# Eagle_LEDCUBE2.net
KiCad netlist of a schematic drawn in EAGLE
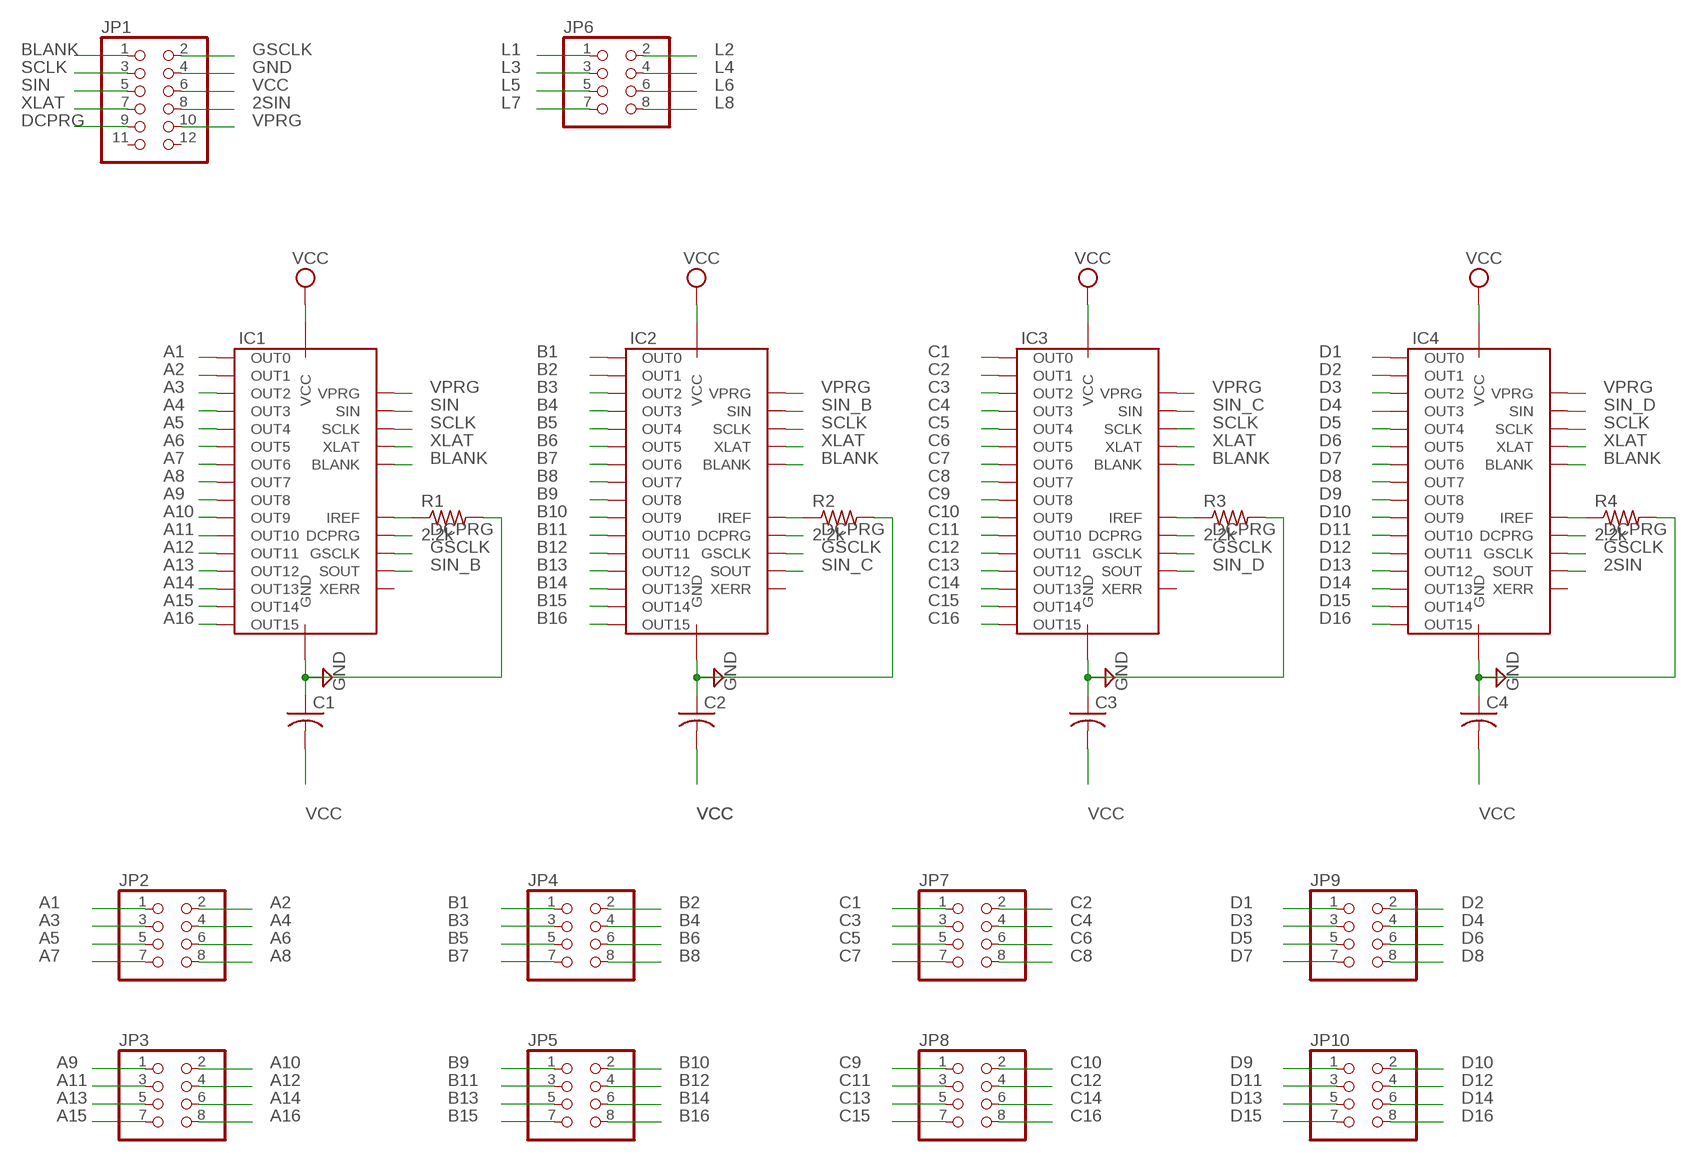
[diagram p0: schematic, sheet 1]
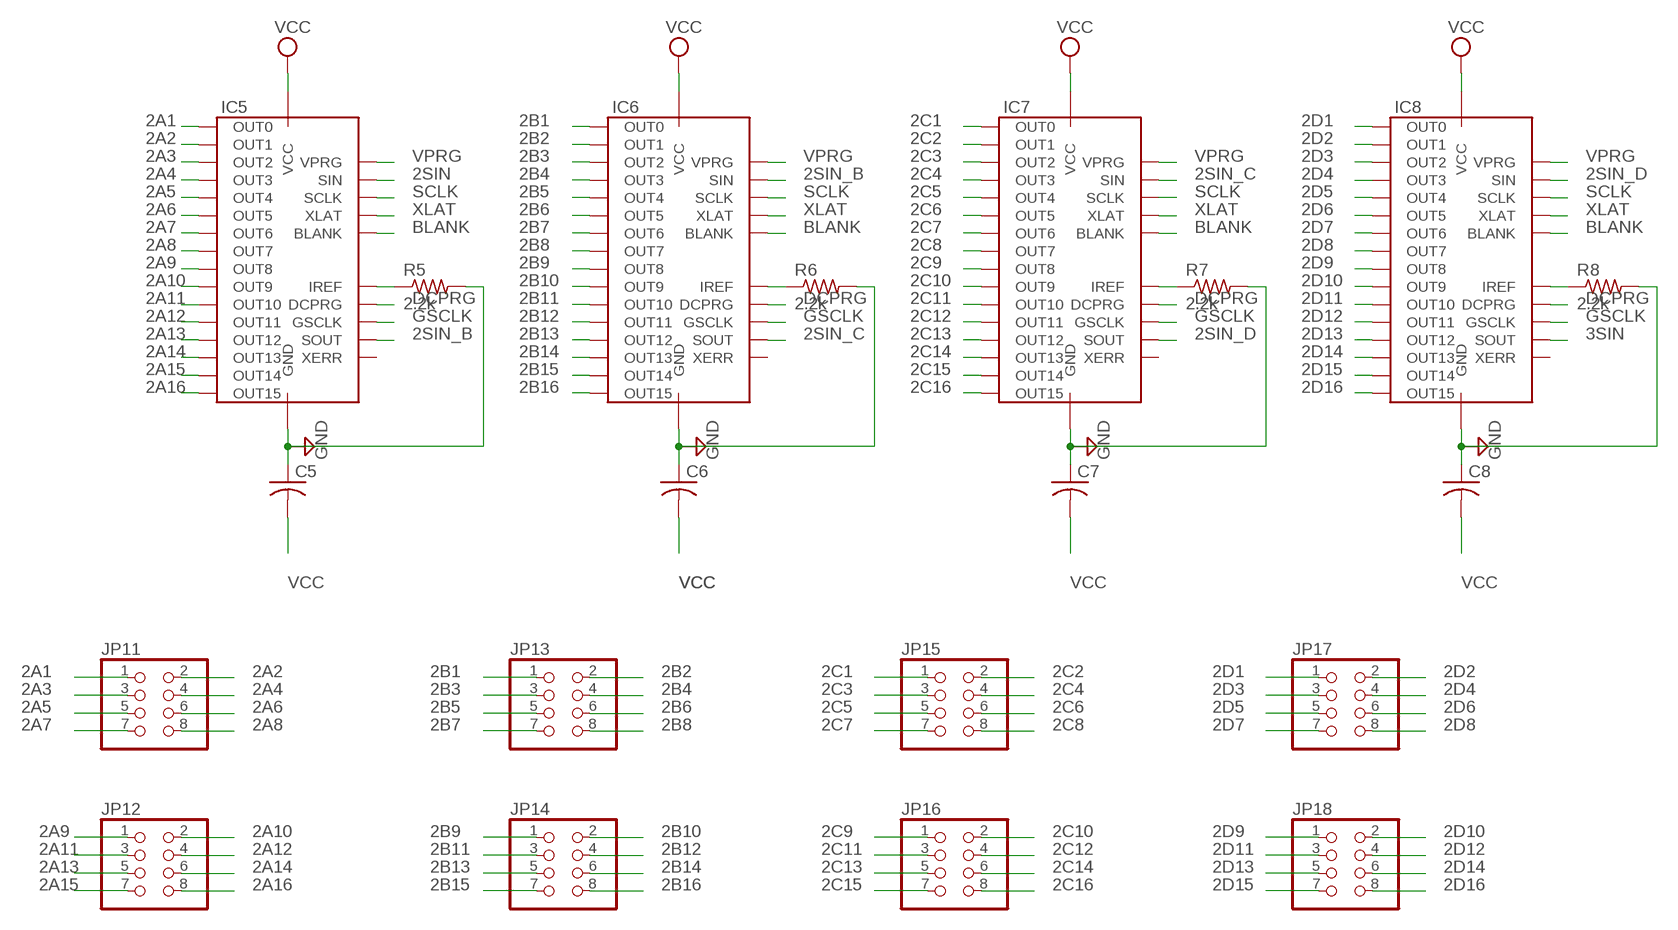
[diagram p1: schematic, sheet 2]
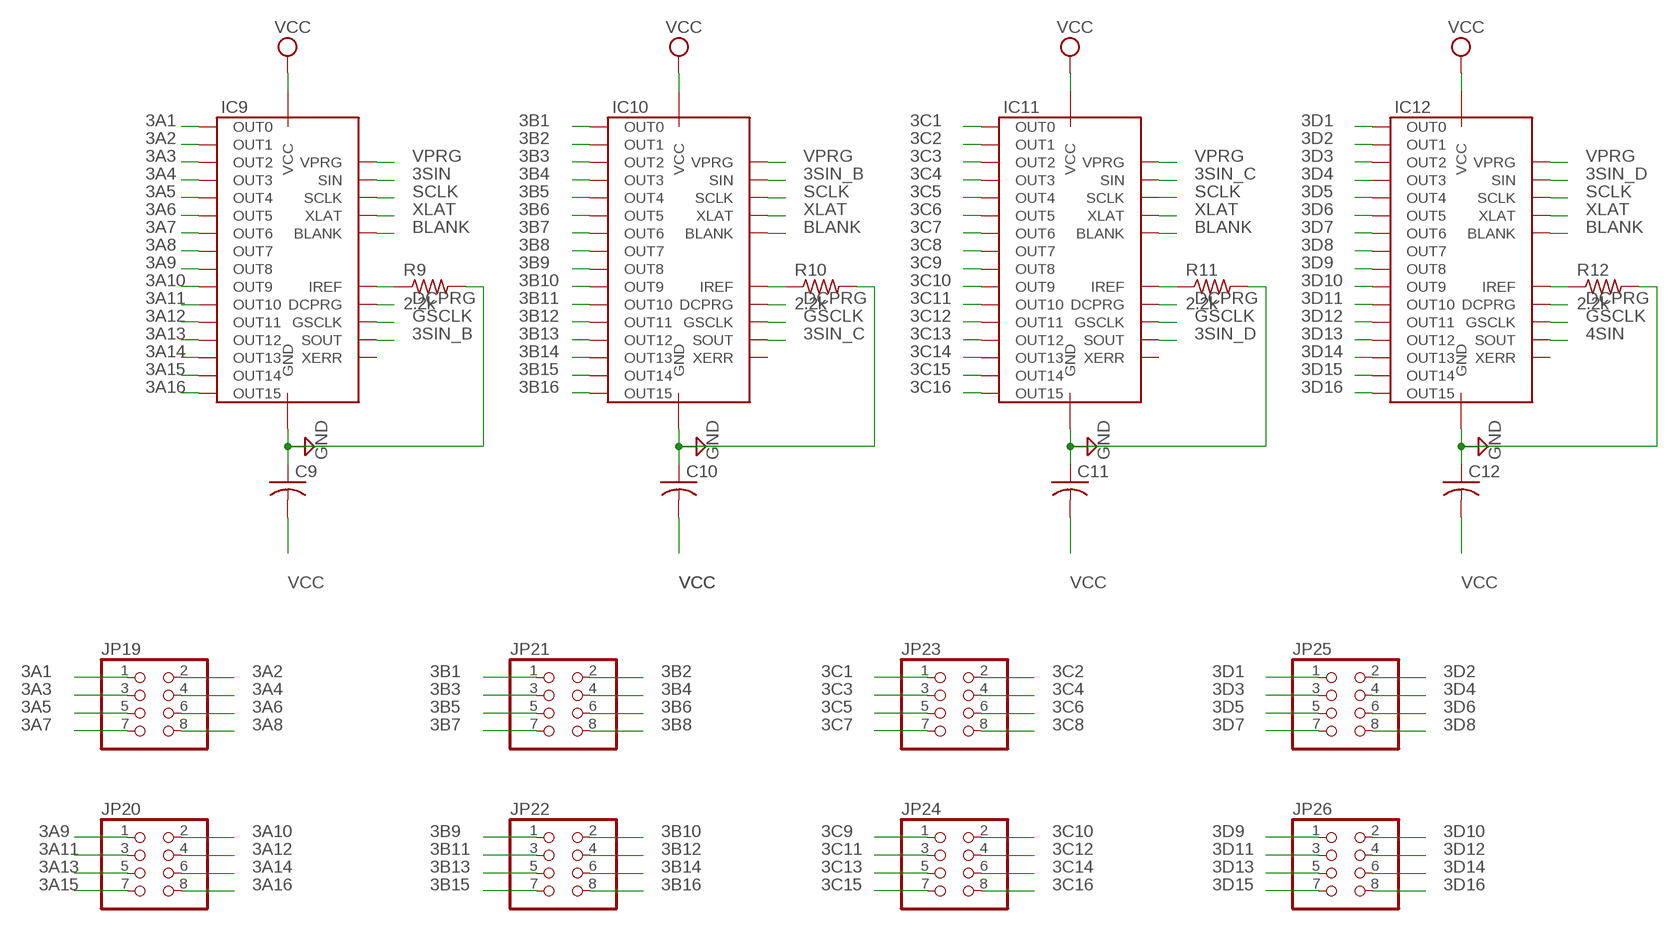
[diagram p2: schematic, sheet 3]
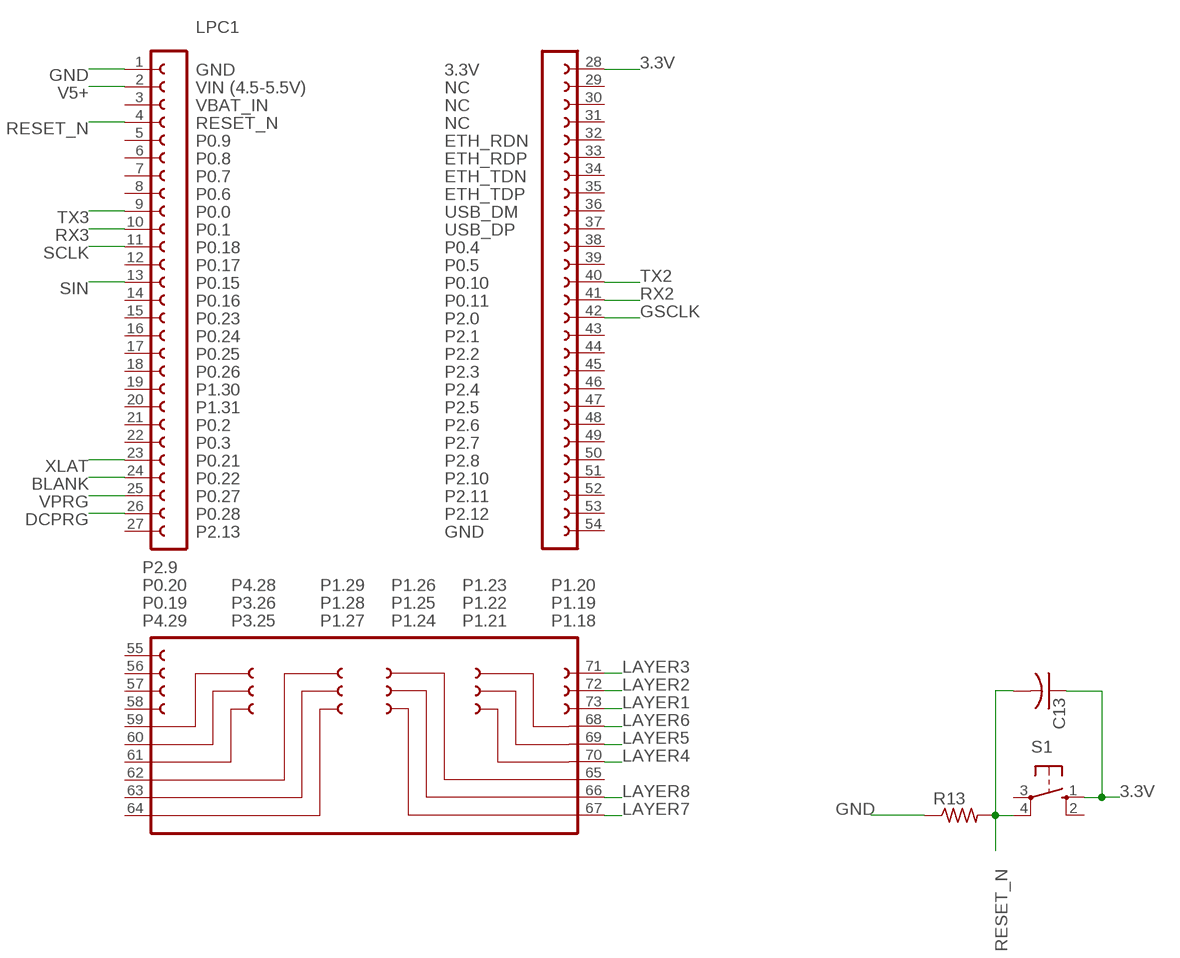
[diagram p3: schematic, sheet 4]
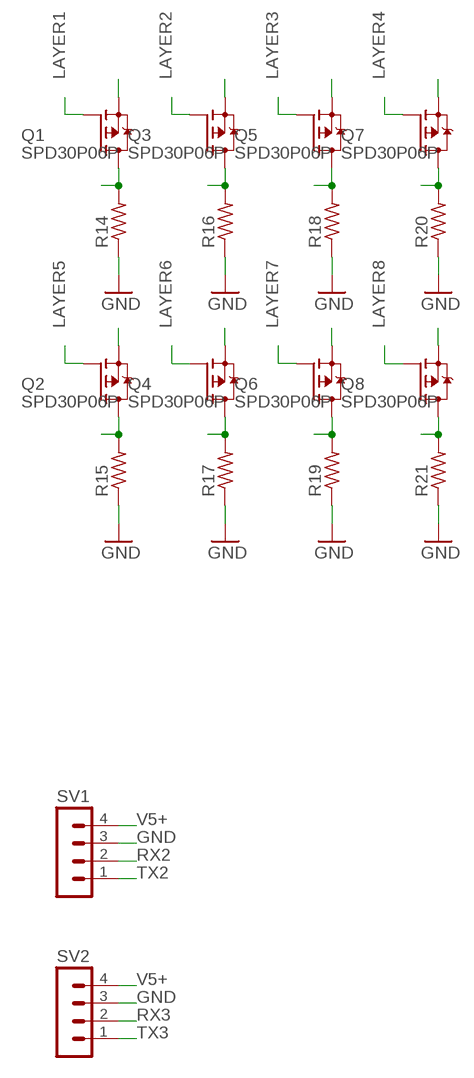
[diagram p4: schematic, sheet 5]
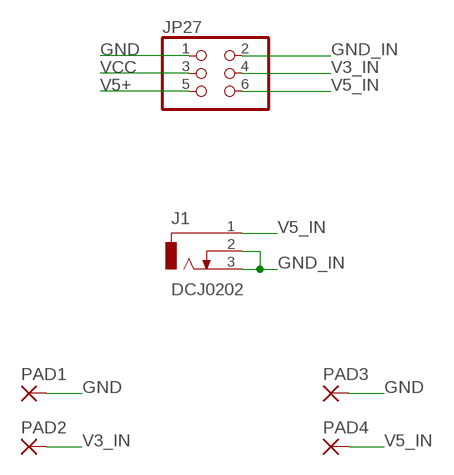
[diagram p5: schematic, sheet 6]

(export (version "E")
  (design (tool "Eeschema 10.0.6"))
  (components
    (comp (ref "Q1")
      (value "SPD30P06P")
      (footprint "eagle-import:TO251AA")
      (libsource (lib "eagle-import") (part "SPD30P06P"))
    )
    (comp (ref "Q2")
      (value "SPD30P06P")
      (footprint "eagle-import:TO251AA")
      (libsource (lib "eagle-import") (part "SPD30P06P"))
    )
    (comp (ref "Q3")
      (value "SPD30P06P")
      (footprint "eagle-import:TO251AA")
      (libsource (lib "eagle-import") (part "SPD30P06P"))
    )
    (comp (ref "Q4")
      (value "SPD30P06P")
      (footprint "eagle-import:TO251AA")
      (libsource (lib "eagle-import") (part "SPD30P06P"))
    )
    (comp (ref "Q5")
      (value "SPD30P06P")
      (footprint "eagle-import:TO251AA")
      (libsource (lib "eagle-import") (part "SPD30P06P"))
    )
    (comp (ref "Q6")
      (value "SPD30P06P")
      (footprint "eagle-import:TO251AA")
      (libsource (lib "eagle-import") (part "SPD30P06P"))
    )
    (comp (ref "Q7")
      (value "SPD30P06P")
      (footprint "eagle-import:TO251AA")
      (libsource (lib "eagle-import") (part "SPD30P06P"))
    )
    (comp (ref "Q8")
      (value "SPD30P06P")
      (footprint "eagle-import:TO251AA")
      (libsource (lib "eagle-import") (part "SPD30P06P"))
    )
    (comp (ref "R14")
      (value "R-US_R0805")
      (footprint "eagle-import:R0805")
      (libsource (lib "eagle-import") (part "resistor_R-US_R0805"))
    )
    (comp (ref "R15")
      (value "R-US_R0805")
      (footprint "eagle-import:R0805")
      (libsource (lib "eagle-import") (part "resistor_R-US_R0805"))
    )
    (comp (ref "R16")
      (value "R-US_R0805")
      (footprint "eagle-import:R0805")
      (libsource (lib "eagle-import") (part "resistor_R-US_R0805"))
    )
    (comp (ref "R17")
      (value "R-US_R0805")
      (footprint "eagle-import:R0805")
      (libsource (lib "eagle-import") (part "resistor_R-US_R0805"))
    )
    (comp (ref "R18")
      (value "R-US_R0805")
      (footprint "eagle-import:R0805")
      (libsource (lib "eagle-import") (part "resistor_R-US_R0805"))
    )
    (comp (ref "R19")
      (value "R-US_R0805")
      (footprint "eagle-import:R0805")
      (libsource (lib "eagle-import") (part "resistor_R-US_R0805"))
    )
    (comp (ref "R20")
      (value "R-US_R0805")
      (footprint "eagle-import:R0805")
      (libsource (lib "eagle-import") (part "resistor_R-US_R0805"))
    )
    (comp (ref "R21")
      (value "R-US_R0805")
      (footprint "eagle-import:R0805")
      (libsource (lib "eagle-import") (part "resistor_R-US_R0805"))
    )
    (comp (ref "SV1")
      (value "MA04-1")
      (footprint "eagle-import:MA04-1")
      (libsource (lib "eagle-import") (part "MA04-1"))
    )
    (comp (ref "SV2")
      (value "MA04-1")
      (footprint "eagle-import:MA04-1")
      (libsource (lib "eagle-import") (part "MA04-1"))
    )
    (comp (ref "C5")
      (value "C-USC0805K")
      (footprint "eagle-import:C0805K")
      (libsource (lib "eagle-import") (part "resistor_C-USC0805K"))
    )
    (comp (ref "C6")
      (value "C-USC0805K")
      (footprint "eagle-import:C0805K")
      (libsource (lib "eagle-import") (part "resistor_C-USC0805K"))
    )
    (comp (ref "C7")
      (value "C-USC0805K")
      (footprint "eagle-import:C0805K")
      (libsource (lib "eagle-import") (part "resistor_C-USC0805K"))
    )
    (comp (ref "C8")
      (value "C-USC0805K")
      (footprint "eagle-import:C0805K")
      (libsource (lib "eagle-import") (part "resistor_C-USC0805K"))
    )
    (comp (ref "IC5")
      (value "IC-PACKAGE_DIL28-1")
      (footprint "eagle-import:IC-SSOP28")
      (libsource (lib "eagle-import") (part "IC-PACKAGE_DIL28-1"))
    )
    (comp (ref "IC6")
      (value "IC-PACKAGE_DIL28-1")
      (footprint "eagle-import:IC-SSOP28")
      (libsource (lib "eagle-import") (part "IC-PACKAGE_DIL28-1"))
    )
    (comp (ref "IC7")
      (value "IC-PACKAGE_DIL28-1")
      (footprint "eagle-import:IC-SSOP28")
      (libsource (lib "eagle-import") (part "IC-PACKAGE_DIL28-1"))
    )
    (comp (ref "IC8")
      (value "IC-PACKAGE_DIL28-1")
      (footprint "eagle-import:IC-SSOP28")
      (libsource (lib "eagle-import") (part "IC-PACKAGE_DIL28-1"))
    )
    (comp (ref "JP11")
      (value "PINHD-2X4")
      (footprint "eagle-import:2X04")
      (libsource (lib "eagle-import") (part "PINHD-2X4"))
    )
    (comp (ref "JP12")
      (value "PINHD-2X4")
      (footprint "eagle-import:2X04")
      (libsource (lib "eagle-import") (part "PINHD-2X4"))
    )
    (comp (ref "JP13")
      (value "PINHD-2X4")
      (footprint "eagle-import:2X04")
      (libsource (lib "eagle-import") (part "PINHD-2X4"))
    )
    (comp (ref "JP14")
      (value "PINHD-2X4")
      (footprint "eagle-import:2X04")
      (libsource (lib "eagle-import") (part "PINHD-2X4"))
    )
    (comp (ref "JP15")
      (value "PINHD-2X4")
      (footprint "eagle-import:2X04")
      (libsource (lib "eagle-import") (part "PINHD-2X4"))
    )
    (comp (ref "JP16")
      (value "PINHD-2X4")
      (footprint "eagle-import:2X04")
      (libsource (lib "eagle-import") (part "PINHD-2X4"))
    )
    (comp (ref "JP17")
      (value "PINHD-2X4")
      (footprint "eagle-import:2X04")
      (libsource (lib "eagle-import") (part "PINHD-2X4"))
    )
    (comp (ref "JP18")
      (value "PINHD-2X4")
      (footprint "eagle-import:2X04")
      (libsource (lib "eagle-import") (part "PINHD-2X4"))
    )
    (comp (ref "R5")
      (value "2.2k")
      (footprint "eagle-import:R0805")
      (libsource (lib "eagle-import") (part "resistor_R-US_R0805"))
    )
    (comp (ref "R6")
      (value "2.2k")
      (footprint "eagle-import:R0805")
      (libsource (lib "eagle-import") (part "resistor_R-US_R0805"))
    )
    (comp (ref "R7")
      (value "2.2k")
      (footprint "eagle-import:R0805")
      (libsource (lib "eagle-import") (part "resistor_R-US_R0805"))
    )
    (comp (ref "R8")
      (value "2.2k")
      (footprint "eagle-import:R0805")
      (libsource (lib "eagle-import") (part "resistor_R-US_R0805"))
    )
    (comp (ref "C9")
      (value "C-USC0805K")
      (footprint "eagle-import:C0805K")
      (libsource (lib "eagle-import") (part "resistor_C-USC0805K"))
    )
    (comp (ref "C10")
      (value "C-USC0805K")
      (footprint "eagle-import:C0805K")
      (libsource (lib "eagle-import") (part "resistor_C-USC0805K"))
    )
    (comp (ref "C11")
      (value "C-USC0805K")
      (footprint "eagle-import:C0805K")
      (libsource (lib "eagle-import") (part "resistor_C-USC0805K"))
    )
    (comp (ref "C12")
      (value "C-USC0805K")
      (footprint "eagle-import:C0805K")
      (libsource (lib "eagle-import") (part "resistor_C-USC0805K"))
    )
    (comp (ref "IC9")
      (value "IC-PACKAGE_DIL28-1")
      (footprint "eagle-import:IC-SSOP28")
      (libsource (lib "eagle-import") (part "IC-PACKAGE_DIL28-1"))
    )
    (comp (ref "IC10")
      (value "IC-PACKAGE_DIL28-1")
      (footprint "eagle-import:IC-SSOP28")
      (libsource (lib "eagle-import") (part "IC-PACKAGE_DIL28-1"))
    )
    (comp (ref "IC11")
      (value "IC-PACKAGE_DIL28-1")
      (footprint "eagle-import:IC-SSOP28")
      (libsource (lib "eagle-import") (part "IC-PACKAGE_DIL28-1"))
    )
    (comp (ref "IC12")
      (value "IC-PACKAGE_DIL28-1")
      (footprint "eagle-import:IC-SSOP28")
      (libsource (lib "eagle-import") (part "IC-PACKAGE_DIL28-1"))
    )
    (comp (ref "JP19")
      (value "PINHD-2X4")
      (footprint "eagle-import:2X04")
      (libsource (lib "eagle-import") (part "PINHD-2X4"))
    )
    (comp (ref "JP20")
      (value "PINHD-2X4")
      (footprint "eagle-import:2X04")
      (libsource (lib "eagle-import") (part "PINHD-2X4"))
    )
    (comp (ref "JP21")
      (value "PINHD-2X4")
      (footprint "eagle-import:2X04")
      (libsource (lib "eagle-import") (part "PINHD-2X4"))
    )
    (comp (ref "JP22")
      (value "PINHD-2X4")
      (footprint "eagle-import:2X04")
      (libsource (lib "eagle-import") (part "PINHD-2X4"))
    )
    (comp (ref "JP23")
      (value "PINHD-2X4")
      (footprint "eagle-import:2X04")
      (libsource (lib "eagle-import") (part "PINHD-2X4"))
    )
    (comp (ref "JP24")
      (value "PINHD-2X4")
      (footprint "eagle-import:2X04")
      (libsource (lib "eagle-import") (part "PINHD-2X4"))
    )
    (comp (ref "JP25")
      (value "PINHD-2X4")
      (footprint "eagle-import:2X04")
      (libsource (lib "eagle-import") (part "PINHD-2X4"))
    )
    (comp (ref "JP26")
      (value "PINHD-2X4")
      (footprint "eagle-import:2X04")
      (libsource (lib "eagle-import") (part "PINHD-2X4"))
    )
    (comp (ref "R9")
      (value "2.2k")
      (footprint "eagle-import:R0805")
      (libsource (lib "eagle-import") (part "resistor_R-US_R0805"))
    )
    (comp (ref "R10")
      (value "2.2k")
      (footprint "eagle-import:R0805")
      (libsource (lib "eagle-import") (part "resistor_R-US_R0805"))
    )
    (comp (ref "R11")
      (value "2.2k")
      (footprint "eagle-import:R0805")
      (libsource (lib "eagle-import") (part "resistor_R-US_R0805"))
    )
    (comp (ref "R12")
      (value "2.2k")
      (footprint "eagle-import:R0805")
      (libsource (lib "eagle-import") (part "resistor_R-US_R0805"))
    )
    (comp (ref "J1")
      (value "DCJ0202")
      (footprint "eagle-import:DCJ0202")
      (libsource (lib "eagle-import") (part "DCJ0202"))
    )
    (comp (ref "JP27")
      (value "PINHD-2X3")
      (footprint "eagle-import:2X03")
      (libsource (lib "eagle-import") (part "PINHD-2X3"))
    )
    (comp (ref "PAD1")
      (value "3,81/1,3")
      (footprint "eagle-import:3,81_1,3")
      (libsource (lib "eagle-import") (part "3,81/1,3"))
    )
    (comp (ref "PAD2")
      (value "3,81/1,3")
      (footprint "eagle-import:3,81_1,3")
      (libsource (lib "eagle-import") (part "3,81/1,3"))
    )
    (comp (ref "PAD3")
      (value "3,81/1,3")
      (footprint "eagle-import:3,81_1,3")
      (libsource (lib "eagle-import") (part "3,81/1,3"))
    )
    (comp (ref "PAD4")
      (value "3,81/1,3")
      (footprint "eagle-import:3,81_1,3")
      (libsource (lib "eagle-import") (part "3,81/1,3"))
    )
    (comp (ref "C1")
      (value "C-USC0805K")
      (footprint "eagle-import:C0805K")
      (libsource (lib "eagle-import") (part "resistor_C-USC0805K"))
    )
    (comp (ref "C2")
      (value "C-USC0805K")
      (footprint "eagle-import:C0805K")
      (libsource (lib "eagle-import") (part "resistor_C-USC0805K"))
    )
    (comp (ref "C3")
      (value "C-USC0805K")
      (footprint "eagle-import:C0805K")
      (libsource (lib "eagle-import") (part "resistor_C-USC0805K"))
    )
    (comp (ref "C4")
      (value "C-USC0805K")
      (footprint "eagle-import:C0805K")
      (libsource (lib "eagle-import") (part "resistor_C-USC0805K"))
    )
    (comp (ref "IC1")
      (value "IC-PACKAGE_DIL28-1")
      (footprint "eagle-import:IC-SSOP28")
      (libsource (lib "eagle-import") (part "IC-PACKAGE_DIL28-1"))
    )
    (comp (ref "IC2")
      (value "IC-PACKAGE_DIL28-1")
      (footprint "eagle-import:IC-SSOP28")
      (libsource (lib "eagle-import") (part "IC-PACKAGE_DIL28-1"))
    )
    (comp (ref "IC3")
      (value "IC-PACKAGE_DIL28-1")
      (footprint "eagle-import:IC-SSOP28")
      (libsource (lib "eagle-import") (part "IC-PACKAGE_DIL28-1"))
    )
    (comp (ref "IC4")
      (value "IC-PACKAGE_DIL28-1")
      (footprint "eagle-import:IC-SSOP28")
      (libsource (lib "eagle-import") (part "IC-PACKAGE_DIL28-1"))
    )
    (comp (ref "JP1")
      (value "PINHD-2X6")
      (footprint "eagle-import:2X06")
      (libsource (lib "eagle-import") (part "PINHD-2X6"))
    )
    (comp (ref "JP2")
      (value "PINHD-2X4")
      (footprint "eagle-import:2X04")
      (libsource (lib "eagle-import") (part "PINHD-2X4"))
    )
    (comp (ref "JP3")
      (value "PINHD-2X4")
      (footprint "eagle-import:2X04")
      (libsource (lib "eagle-import") (part "PINHD-2X4"))
    )
    (comp (ref "JP4")
      (value "PINHD-2X4")
      (footprint "eagle-import:2X04")
      (libsource (lib "eagle-import") (part "PINHD-2X4"))
    )
    (comp (ref "JP5")
      (value "PINHD-2X4")
      (footprint "eagle-import:2X04")
      (libsource (lib "eagle-import") (part "PINHD-2X4"))
    )
    (comp (ref "JP6")
      (value "PINHD-2X4")
      (footprint "eagle-import:2X04")
      (libsource (lib "eagle-import") (part "PINHD-2X4"))
    )
    (comp (ref "JP7")
      (value "PINHD-2X4")
      (footprint "eagle-import:2X04")
      (libsource (lib "eagle-import") (part "PINHD-2X4"))
    )
    (comp (ref "JP8")
      (value "PINHD-2X4")
      (footprint "eagle-import:2X04")
      (libsource (lib "eagle-import") (part "PINHD-2X4"))
    )
    (comp (ref "JP9")
      (value "PINHD-2X4")
      (footprint "eagle-import:2X04")
      (libsource (lib "eagle-import") (part "PINHD-2X4"))
    )
    (comp (ref "JP10")
      (value "PINHD-2X4")
      (footprint "eagle-import:2X04")
      (libsource (lib "eagle-import") (part "PINHD-2X4"))
    )
    (comp (ref "R1")
      (value "2.2k")
      (footprint "eagle-import:R0805")
      (libsource (lib "eagle-import") (part "resistor_R-US_R0805"))
    )
    (comp (ref "R2")
      (value "2.2k")
      (footprint "eagle-import:R0805")
      (libsource (lib "eagle-import") (part "resistor_R-US_R0805"))
    )
    (comp (ref "R3")
      (value "2.2k")
      (footprint "eagle-import:R0805")
      (libsource (lib "eagle-import") (part "resistor_R-US_R0805"))
    )
    (comp (ref "R4")
      (value "2.2k")
      (footprint "eagle-import:R0805")
      (libsource (lib "eagle-import") (part "resistor_R-US_R0805"))
    )
    (comp (ref "C13")
      (value "C-USC0805K")
      (footprint "eagle-import:C0805K")
      (libsource (lib "eagle-import") (part "C-USC0805K"))
    )
    (comp (ref "LPC1")
      (value "LPCXPRESSO_LPC1769")
      (footprint "eagle-import:LPCXPRESSO_LPC1769")
      (libsource (lib "eagle-import") (part "LPCXPRESSO_LPC1769"))
    )
    (comp (ref "R13")
      (value "R-US_R0805")
      (footprint "eagle-import:R0805")
      (libsource (lib "eagle-import") (part "R-US_R0805"))
    )
    (comp (ref "S1")
      (value "10-XX")
      (footprint "eagle-import:B3F-10XX")
      (fields (field (name "MPN") "B3F-1000"))
      (libsource (lib "eagle-import") (part "10-XX"))
    )
  )
  (nets
    (net (code "1") (name "2A1") (class "Default")
      (node (ref "IC5") (pin "7") (pinfunction "OUT0_7") (pintype "open_collector"))
      (node (ref "JP11") (pin "1") (pinfunction "1_1") (pintype "passive"))
    )
    (net (code "2") (name "2A2") (class "Default")
      (node (ref "IC5") (pin "8") (pinfunction "OUT1_8") (pintype "open_collector"))
      (node (ref "JP11") (pin "2") (pinfunction "2_2") (pintype "passive"))
    )
    (net (code "3") (name "2A3") (class "Default")
      (node (ref "IC5") (pin "9") (pinfunction "OUT2_9") (pintype "open_collector"))
      (node (ref "JP11") (pin "3") (pinfunction "3_3") (pintype "passive"))
    )
    (net (code "4") (name "2A4") (class "Default")
      (node (ref "IC5") (pin "10") (pinfunction "OUT3_10") (pintype "open_collector"))
      (node (ref "JP11") (pin "4") (pinfunction "4_4") (pintype "passive"))
    )
    (net (code "5") (name "2A5") (class "Default")
      (node (ref "IC5") (pin "11") (pinfunction "OUT4_11") (pintype "open_collector"))
      (node (ref "JP11") (pin "5") (pinfunction "5_5") (pintype "passive"))
    )
    (net (code "6") (name "2A6") (class "Default")
      (node (ref "IC5") (pin "12") (pinfunction "OUT5_12") (pintype "open_collector"))
      (node (ref "JP11") (pin "6") (pinfunction "6_6") (pintype "passive"))
    )
    (net (code "7") (name "2A7") (class "Default")
      (node (ref "IC5") (pin "13") (pinfunction "OUT6_13") (pintype "open_collector"))
      (node (ref "JP11") (pin "7") (pinfunction "7_7") (pintype "passive"))
    )
    (net (code "8") (name "2A8") (class "Default")
      (node (ref "IC5") (pin "14") (pinfunction "OUT7_14") (pintype "open_collector"))
      (node (ref "JP11") (pin "8") (pinfunction "8_8") (pintype "passive"))
    )
    (net (code "9") (name "2A9") (class "Default")
      (node (ref "IC5") (pin "15") (pinfunction "OUT8_15") (pintype "open_collector"))
      (node (ref "JP12") (pin "1") (pinfunction "1_1") (pintype "passive"))
    )
    (net (code "10") (name "2A10") (class "Default")
      (node (ref "IC5") (pin "16") (pinfunction "OUT9_16") (pintype "open_collector"))
      (node (ref "JP12") (pin "2") (pinfunction "2_2") (pintype "passive"))
    )
    (net (code "11") (name "2A11") (class "Default")
      (node (ref "IC5") (pin "17") (pinfunction "OUT10_17") (pintype "open_collector"))
      (node (ref "JP12") (pin "3") (pinfunction "3_3") (pintype "passive"))
    )
    (net (code "12") (name "2A12") (class "Default")
      (node (ref "IC5") (pin "18") (pinfunction "OUT11_18") (pintype "open_collector"))
      (node (ref "JP12") (pin "4") (pinfunction "4_4") (pintype "passive"))
    )
    (net (code "13") (name "2A13") (class "Default")
      (node (ref "IC5") (pin "19") (pinfunction "OUT12_19") (pintype "open_collector"))
      (node (ref "JP12") (pin "5") (pinfunction "5_5") (pintype "passive"))
    )
    (net (code "14") (name "2A14") (class "Default")
      (node (ref "IC5") (pin "20") (pinfunction "OUT13_20") (pintype "open_collector"))
      (node (ref "JP12") (pin "6") (pinfunction "6_6") (pintype "passive"))
    )
    (net (code "15") (name "2A15") (class "Default")
      (node (ref "IC5") (pin "21") (pinfunction "OUT14_21") (pintype "open_collector"))
      (node (ref "JP12") (pin "7") (pinfunction "7_7") (pintype "passive"))
    )
    (net (code "16") (name "2A16") (class "Default")
      (node (ref "IC5") (pin "22") (pinfunction "OUT15_22") (pintype "open_collector"))
      (node (ref "JP12") (pin "8") (pinfunction "8_8") (pintype "passive"))
    )
    (net (code "17") (name "2B1") (class "Default")
      (node (ref "IC6") (pin "7") (pinfunction "OUT0_7") (pintype "open_collector"))
      (node (ref "JP13") (pin "1") (pinfunction "1_1") (pintype "passive"))
    )
    (net (code "18") (name "2B2") (class "Default")
      (node (ref "IC6") (pin "8") (pinfunction "OUT1_8") (pintype "open_collector"))
      (node (ref "JP13") (pin "2") (pinfunction "2_2") (pintype "passive"))
    )
    (net (code "19") (name "2B3") (class "Default")
      (node (ref "IC6") (pin "9") (pinfunction "OUT2_9") (pintype "open_collector"))
      (node (ref "JP13") (pin "3") (pinfunction "3_3") (pintype "passive"))
    )
    (net (code "20") (name "2B4") (class "Default")
      (node (ref "IC6") (pin "10") (pinfunction "OUT3_10") (pintype "open_collector"))
      (node (ref "JP13") (pin "4") (pinfunction "4_4") (pintype "passive"))
    )
    (net (code "21") (name "2B5") (class "Default")
      (node (ref "IC6") (pin "11") (pinfunction "OUT4_11") (pintype "open_collector"))
      (node (ref "JP13") (pin "5") (pinfunction "5_5") (pintype "passive"))
    )
    (net (code "22") (name "2B6") (class "Default")
      (node (ref "IC6") (pin "12") (pinfunction "OUT5_12") (pintype "open_collector"))
      (node (ref "JP13") (pin "6") (pinfunction "6_6") (pintype "passive"))
    )
    (net (code "23") (name "2B7") (class "Default")
      (node (ref "IC6") (pin "13") (pinfunction "OUT6_13") (pintype "open_collector"))
      (node (ref "JP13") (pin "7") (pinfunction "7_7") (pintype "passive"))
    )
    (net (code "24") (name "2B8") (class "Default")
      (node (ref "IC6") (pin "14") (pinfunction "OUT7_14") (pintype "open_collector"))
      (node (ref "JP13") (pin "8") (pinfunction "8_8") (pintype "passive"))
    )
    (net (code "25") (name "2B9") (class "Default")
      (node (ref "IC6") (pin "15") (pinfunction "OUT8_15") (pintype "open_collector"))
      (node (ref "JP14") (pin "1") (pinfunction "1_1") (pintype "passive"))
    )
    (net (code "26") (name "2B10") (class "Default")
      (node (ref "IC6") (pin "16") (pinfunction "OUT9_16") (pintype "open_collector"))
      (node (ref "JP14") (pin "2") (pinfunction "2_2") (pintype "passive"))
    )
    (net (code "27") (name "2B11") (class "Default")
      (node (ref "IC6") (pin "17") (pinfunction "OUT10_17") (pintype "open_collector"))
      (node (ref "JP14") (pin "3") (pinfunction "3_3") (pintype "passive"))
    )
    (net (code "28") (name "2B12") (class "Default")
      (node (ref "IC6") (pin "18") (pinfunction "OUT11_18") (pintype "open_collector"))
      (node (ref "JP14") (pin "4") (pinfunction "4_4") (pintype "passive"))
    )
    (net (code "29") (name "2B13") (class "Default")
      (node (ref "IC6") (pin "19") (pinfunction "OUT12_19") (pintype "open_collector"))
      (node (ref "JP14") (pin "5") (pinfunction "5_5") (pintype "passive"))
    )
    (net (code "30") (name "2B14") (class "Default")
      (node (ref "IC6") (pin "20") (pinfunction "OUT13_20") (pintype "open_collector"))
      (node (ref "JP14") (pin "6") (pinfunction "6_6") (pintype "passive"))
    )
    (net (code "31") (name "2B15") (class "Default")
      (node (ref "IC6") (pin "21") (pinfunction "OUT14_21") (pintype "open_collector"))
      (node (ref "JP14") (pin "7") (pinfunction "7_7") (pintype "passive"))
    )
    (net (code "32") (name "2B16") (class "Default")
      (node (ref "IC6") (pin "22") (pinfunction "OUT15_22") (pintype "open_collector"))
      (node (ref "JP14") (pin "8") (pinfunction "8_8") (pintype "passive"))
    )
    (net (code "33") (name "2C1") (class "Default")
      (node (ref "IC7") (pin "7") (pinfunction "OUT0_7") (pintype "open_collector"))
      (node (ref "JP15") (pin "1") (pinfunction "1_1") (pintype "passive"))
    )
    (net (code "34") (name "2C2") (class "Default")
      (node (ref "IC7") (pin "8") (pinfunction "OUT1_8") (pintype "open_collector"))
      (node (ref "JP15") (pin "2") (pinfunction "2_2") (pintype "passive"))
    )
    (net (code "35") (name "2C3") (class "Default")
      (node (ref "IC7") (pin "9") (pinfunction "OUT2_9") (pintype "open_collector"))
      (node (ref "JP15") (pin "3") (pinfunction "3_3") (pintype "passive"))
    )
    (net (code "36") (name "2C4") (class "Default")
      (node (ref "IC7") (pin "10") (pinfunction "OUT3_10") (pintype "open_collector"))
      (node (ref "JP15") (pin "4") (pinfunction "4_4") (pintype "passive"))
    )
    (net (code "37") (name "2C5") (class "Default")
      (node (ref "IC7") (pin "11") (pinfunction "OUT4_11") (pintype "open_collector"))
      (node (ref "JP15") (pin "5") (pinfunction "5_5") (pintype "passive"))
    )
    (net (code "38") (name "2C6") (class "Default")
      (node (ref "IC7") (pin "12") (pinfunction "OUT5_12") (pintype "open_collector"))
      (node (ref "JP15") (pin "6") (pinfunction "6_6") (pintype "passive"))
    )
    (net (code "39") (name "2C7") (class "Default")
      (node (ref "IC7") (pin "13") (pinfunction "OUT6_13") (pintype "open_collector"))
      (node (ref "JP15") (pin "7") (pinfunction "7_7") (pintype "passive"))
    )
    (net (code "40") (name "2C8") (class "Default")
      (node (ref "IC7") (pin "14") (pinfunction "OUT7_14") (pintype "open_collector"))
      (node (ref "JP15") (pin "8") (pinfunction "8_8") (pintype "passive"))
    )
    (net (code "41") (name "2C9") (class "Default")
      (node (ref "IC7") (pin "15") (pinfunction "OUT8_15") (pintype "open_collector"))
      (node (ref "JP16") (pin "1") (pinfunction "1_1") (pintype "passive"))
    )
    (net (code "42") (name "2C10") (class "Default")
      (node (ref "IC7") (pin "16") (pinfunction "OUT9_16") (pintype "open_collector"))
      (node (ref "JP16") (pin "2") (pinfunction "2_2") (pintype "passive"))
    )
    (net (code "43") (name "2C11") (class "Default")
      (node (ref "IC7") (pin "17") (pinfunction "OUT10_17") (pintype "open_collector"))
      (node (ref "JP16") (pin "3") (pinfunction "3_3") (pintype "passive"))
    )
    (net (code "44") (name "2C12") (class "Default")
      (node (ref "IC7") (pin "18") (pinfunction "OUT11_18") (pintype "open_collector"))
      (node (ref "JP16") (pin "4") (pinfunction "4_4") (pintype "passive"))
    )
    (net (code "45") (name "2C13") (class "Default")
      (node (ref "IC7") (pin "19") (pinfunction "OUT12_19") (pintype "open_collector"))
      (node (ref "JP16") (pin "5") (pinfunction "5_5") (pintype "passive"))
    )
    (net (code "46") (name "2C14") (class "Default")
      (node (ref "IC7") (pin "20") (pinfunction "OUT13_20") (pintype "open_collector"))
      (node (ref "JP16") (pin "6") (pinfunction "6_6") (pintype "passive"))
    )
    (net (code "47") (name "2C15") (class "Default")
      (node (ref "IC7") (pin "21") (pinfunction "OUT14_21") (pintype "open_collector"))
      (node (ref "JP16") (pin "7") (pinfunction "7_7") (pintype "passive"))
    )
    (net (code "48") (name "2C16") (class "Default")
      (node (ref "IC7") (pin "22") (pinfunction "OUT15_22") (pintype "open_collector"))
      (node (ref "JP16") (pin "8") (pinfunction "8_8") (pintype "passive"))
    )
    (net (code "49") (name "2D1") (class "Default")
      (node (ref "IC8") (pin "7") (pinfunction "OUT0_7") (pintype "open_collector"))
      (node (ref "JP17") (pin "1") (pinfunction "1_1") (pintype "passive"))
    )
    (net (code "50") (name "2D2") (class "Default")
      (node (ref "IC8") (pin "8") (pinfunction "OUT1_8") (pintype "open_collector"))
      (node (ref "JP17") (pin "2") (pinfunction "2_2") (pintype "passive"))
    )
    (net (code "51") (name "2D3") (class "Default")
      (node (ref "IC8") (pin "9") (pinfunction "OUT2_9") (pintype "open_collector"))
      (node (ref "JP17") (pin "3") (pinfunction "3_3") (pintype "passive"))
    )
    (net (code "52") (name "2D4") (class "Default")
      (node (ref "IC8") (pin "10") (pinfunction "OUT3_10") (pintype "open_collector"))
      (node (ref "JP17") (pin "4") (pinfunction "4_4") (pintype "passive"))
    )
    (net (code "53") (name "2D5") (class "Default")
      (node (ref "IC8") (pin "11") (pinfunction "OUT4_11") (pintype "open_collector"))
      (node (ref "JP17") (pin "5") (pinfunction "5_5") (pintype "passive"))
    )
    (net (code "54") (name "2D6") (class "Default")
      (node (ref "IC8") (pin "12") (pinfunction "OUT5_12") (pintype "open_collector"))
      (node (ref "JP17") (pin "6") (pinfunction "6_6") (pintype "passive"))
    )
    (net (code "55") (name "2D7") (class "Default")
      (node (ref "IC8") (pin "13") (pinfunction "OUT6_13") (pintype "open_collector"))
      (node (ref "JP17") (pin "7") (pinfunction "7_7") (pintype "passive"))
    )
    (net (code "56") (name "2D8") (class "Default")
      (node (ref "IC8") (pin "14") (pinfunction "OUT7_14") (pintype "open_collector"))
      (node (ref "JP17") (pin "8") (pinfunction "8_8") (pintype "passive"))
    )
    (net (code "57") (name "2D9") (class "Default")
      (node (ref "IC8") (pin "15") (pinfunction "OUT8_15") (pintype "open_collector"))
      (node (ref "JP18") (pin "1") (pinfunction "1_1") (pintype "passive"))
    )
    (net (code "58") (name "2D10") (class "Default")
      (node (ref "IC8") (pin "16") (pinfunction "OUT9_16") (pintype "open_collector"))
      (node (ref "JP18") (pin "2") (pinfunction "2_2") (pintype "passive"))
    )
    (net (code "59") (name "2D11") (class "Default")
      (node (ref "IC8") (pin "17") (pinfunction "OUT10_17") (pintype "open_collector"))
      (node (ref "JP18") (pin "3") (pinfunction "3_3") (pintype "passive"))
    )
    (net (code "60") (name "2D12") (class "Default")
      (node (ref "IC8") (pin "18") (pinfunction "OUT11_18") (pintype "open_collector"))
      (node (ref "JP18") (pin "4") (pinfunction "4_4") (pintype "passive"))
    )
    (net (code "61") (name "2D13") (class "Default")
      (node (ref "IC8") (pin "19") (pinfunction "OUT12_19") (pintype "open_collector"))
      (node (ref "JP18") (pin "5") (pinfunction "5_5") (pintype "passive"))
    )
    (net (code "62") (name "2D14") (class "Default")
      (node (ref "IC8") (pin "20") (pinfunction "OUT13_20") (pintype "open_collector"))
      (node (ref "JP18") (pin "6") (pinfunction "6_6") (pintype "passive"))
    )
    (net (code "63") (name "2D15") (class "Default")
      (node (ref "IC8") (pin "21") (pinfunction "OUT14_21") (pintype "open_collector"))
      (node (ref "JP18") (pin "7") (pinfunction "7_7") (pintype "passive"))
    )
    (net (code "64") (name "2D16") (class "Default")
      (node (ref "IC8") (pin "22") (pinfunction "OUT15_22") (pintype "open_collector"))
      (node (ref "JP18") (pin "8") (pinfunction "8_8") (pintype "passive"))
    )
    (net (code "65") (name "2SIN") (class "Default")
      (node (ref "IC4") (pin "24") (pinfunction "SOUT_24") (pintype "output"))
      (node (ref "IC5") (pin "5") (pinfunction "SIN_5") (pintype "input"))
      (node (ref "JP1") (pin "8") (pinfunction "8_8") (pintype "passive"))
    )
    (net (code "66") (name "2SIN_B") (class "Default")
      (node (ref "IC5") (pin "24") (pinfunction "SOUT_24") (pintype "output"))
      (node (ref "IC6") (pin "5") (pinfunction "SIN_5") (pintype "input"))
    )
    (net (code "67") (name "2SIN_C") (class "Default")
      (node (ref "IC6") (pin "24") (pinfunction "SOUT_24") (pintype "output"))
      (node (ref "IC7") (pin "5") (pinfunction "SIN_5") (pintype "input"))
    )
    (net (code "68") (name "2SIN_D") (class "Default")
      (node (ref "IC7") (pin "24") (pinfunction "SOUT_24") (pintype "output"))
      (node (ref "IC8") (pin "5") (pinfunction "SIN_5") (pintype "input"))
    )
    (net (code "69") (name "3.3V") (class "Default")
      (node (ref "C13") (pin "1") (pinfunction "1_1") (pintype "passive"))
      (node (ref "LPC1") (pin "28") (pinfunction "28_28") (pintype "passive"))
      (node (ref "S1") (pin "1") (pinfunction "S_1") (pintype "passive"))
    )
    (net (code "70") (name "3A1") (class "Default")
      (node (ref "IC9") (pin "7") (pinfunction "OUT0_7") (pintype "open_collector"))
      (node (ref "JP19") (pin "1") (pinfunction "1_1") (pintype "passive"))
    )
    (net (code "71") (name "3A2") (class "Default")
      (node (ref "IC9") (pin "8") (pinfunction "OUT1_8") (pintype "open_collector"))
      (node (ref "JP19") (pin "2") (pinfunction "2_2") (pintype "passive"))
    )
    (net (code "72") (name "3A3") (class "Default")
      (node (ref "IC9") (pin "9") (pinfunction "OUT2_9") (pintype "open_collector"))
      (node (ref "JP19") (pin "3") (pinfunction "3_3") (pintype "passive"))
    )
    (net (code "73") (name "3A4") (class "Default")
      (node (ref "IC9") (pin "10") (pinfunction "OUT3_10") (pintype "open_collector"))
      (node (ref "JP19") (pin "4") (pinfunction "4_4") (pintype "passive"))
    )
    (net (code "74") (name "3A5") (class "Default")
      (node (ref "IC9") (pin "11") (pinfunction "OUT4_11") (pintype "open_collector"))
      (node (ref "JP19") (pin "5") (pinfunction "5_5") (pintype "passive"))
    )
    (net (code "75") (name "3A6") (class "Default")
      (node (ref "IC9") (pin "12") (pinfunction "OUT5_12") (pintype "open_collector"))
      (node (ref "JP19") (pin "6") (pinfunction "6_6") (pintype "passive"))
    )
    (net (code "76") (name "3A7") (class "Default")
      (node (ref "IC9") (pin "13") (pinfunction "OUT6_13") (pintype "open_collector"))
      (node (ref "JP19") (pin "7") (pinfunction "7_7") (pintype "passive"))
    )
    (net (code "77") (name "3A8") (class "Default")
      (node (ref "IC9") (pin "14") (pinfunction "OUT7_14") (pintype "open_collector"))
      (node (ref "JP19") (pin "8") (pinfunction "8_8") (pintype "passive"))
    )
    (net (code "78") (name "3A9") (class "Default")
      (node (ref "IC9") (pin "15") (pinfunction "OUT8_15") (pintype "open_collector"))
      (node (ref "JP20") (pin "1") (pinfunction "1_1") (pintype "passive"))
    )
    (net (code "79") (name "3A10") (class "Default")
      (node (ref "IC9") (pin "16") (pinfunction "OUT9_16") (pintype "open_collector"))
      (node (ref "JP20") (pin "2") (pinfunction "2_2") (pintype "passive"))
    )
    (net (code "80") (name "3A11") (class "Default")
      (node (ref "IC9") (pin "17") (pinfunction "OUT10_17") (pintype "open_collector"))
      (node (ref "JP20") (pin "3") (pinfunction "3_3") (pintype "passive"))
    )
    (net (code "81") (name "3A12") (class "Default")
      (node (ref "IC9") (pin "18") (pinfunction "OUT11_18") (pintype "open_collector"))
      (node (ref "JP20") (pin "4") (pinfunction "4_4") (pintype "passive"))
    )
    (net (code "82") (name "3A13") (class "Default")
      (node (ref "IC9") (pin "19") (pinfunction "OUT12_19") (pintype "open_collector"))
      (node (ref "JP20") (pin "5") (pinfunction "5_5") (pintype "passive"))
    )
    (net (code "83") (name "3A14") (class "Default")
      (node (ref "IC9") (pin "20") (pinfunction "OUT13_20") (pintype "open_collector"))
      (node (ref "JP20") (pin "6") (pinfunction "6_6") (pintype "passive"))
    )
    (net (code "84") (name "3A15") (class "Default")
      (node (ref "IC9") (pin "21") (pinfunction "OUT14_21") (pintype "open_collector"))
      (node (ref "JP20") (pin "7") (pinfunction "7_7") (pintype "passive"))
    )
    (net (code "85") (name "3A16") (class "Default")
      (node (ref "IC9") (pin "22") (pinfunction "OUT15_22") (pintype "open_collector"))
      (node (ref "JP20") (pin "8") (pinfunction "8_8") (pintype "passive"))
    )
    (net (code "86") (name "3B1") (class "Default")
      (node (ref "IC10") (pin "7") (pinfunction "OUT0_7") (pintype "open_collector"))
      (node (ref "JP21") (pin "1") (pinfunction "1_1") (pintype "passive"))
    )
    (net (code "87") (name "3B2") (class "Default")
      (node (ref "IC10") (pin "8") (pinfunction "OUT1_8") (pintype "open_collector"))
      (node (ref "JP21") (pin "2") (pinfunction "2_2") (pintype "passive"))
    )
    (net (code "88") (name "3B3") (class "Default")
      (node (ref "IC10") (pin "9") (pinfunction "OUT2_9") (pintype "open_collector"))
      (node (ref "JP21") (pin "3") (pinfunction "3_3") (pintype "passive"))
    )
    (net (code "89") (name "3B4") (class "Default")
      (node (ref "IC10") (pin "10") (pinfunction "OUT3_10") (pintype "open_collector"))
      (node (ref "JP21") (pin "4") (pinfunction "4_4") (pintype "passive"))
    )
    (net (code "90") (name "3B5") (class "Default")
      (node (ref "IC10") (pin "11") (pinfunction "OUT4_11") (pintype "open_collector"))
      (node (ref "JP21") (pin "5") (pinfunction "5_5") (pintype "passive"))
    )
    (net (code "91") (name "3B6") (class "Default")
      (node (ref "IC10") (pin "12") (pinfunction "OUT5_12") (pintype "open_collector"))
      (node (ref "JP21") (pin "6") (pinfunction "6_6") (pintype "passive"))
    )
    (net (code "92") (name "3B7") (class "Default")
      (node (ref "IC10") (pin "13") (pinfunction "OUT6_13") (pintype "open_collector"))
      (node (ref "JP21") (pin "7") (pinfunction "7_7") (pintype "passive"))
    )
    (net (code "93") (name "3B8") (class "Default")
      (node (ref "IC10") (pin "14") (pinfunction "OUT7_14") (pintype "open_collector"))
      (node (ref "JP21") (pin "8") (pinfunction "8_8") (pintype "passive"))
    )
    (net (code "94") (name "3B9") (class "Default")
      (node (ref "IC10") (pin "15") (pinfunction "OUT8_15") (pintype "open_collector"))
      (node (ref "JP22") (pin "1") (pinfunction "1_1") (pintype "passive"))
    )
    (net (code "95") (name "3B10") (class "Default")
      (node (ref "IC10") (pin "16") (pinfunction "OUT9_16") (pintype "open_collector"))
      (node (ref "JP22") (pin "2") (pinfunction "2_2") (pintype "passive"))
    )
    (net (code "96") (name "3B11") (class "Default")
      (node (ref "IC10") (pin "17") (pinfunction "OUT10_17") (pintype "open_collector"))
      (node (ref "JP22") (pin "3") (pinfunction "3_3") (pintype "passive"))
    )
    (net (code "97") (name "3B12") (class "Default")
      (node (ref "IC10") (pin "18") (pinfunction "OUT11_18") (pintype "open_collector"))
      (node (ref "JP22") (pin "4") (pinfunction "4_4") (pintype "passive"))
    )
    (net (code "98") (name "3B13") (class "Default")
      (node (ref "IC10") (pin "19") (pinfunction "OUT12_19") (pintype "open_collector"))
      (node (ref "JP22") (pin "5") (pinfunction "5_5") (pintype "passive"))
    )
    (net (code "99") (name "3B14") (class "Default")
      (node (ref "IC10") (pin "20") (pinfunction "OUT13_20") (pintype "open_collector"))
      (node (ref "JP22") (pin "6") (pinfunction "6_6") (pintype "passive"))
    )
    (net (code "100") (name "3B15") (class "Default")
      (node (ref "IC10") (pin "21") (pinfunction "OUT14_21") (pintype "open_collector"))
      (node (ref "JP22") (pin "7") (pinfunction "7_7") (pintype "passive"))
    )
    (net (code "101") (name "3B16") (class "Default")
      (node (ref "IC10") (pin "22") (pinfunction "OUT15_22") (pintype "open_collector"))
      (node (ref "JP22") (pin "8") (pinfunction "8_8") (pintype "passive"))
    )
    (net (code "102") (name "3C1") (class "Default")
      (node (ref "IC11") (pin "7") (pinfunction "OUT0_7") (pintype "open_collector"))
      (node (ref "JP23") (pin "1") (pinfunction "1_1") (pintype "passive"))
    )
    (net (code "103") (name "3C2") (class "Default")
      (node (ref "IC11") (pin "8") (pinfunction "OUT1_8") (pintype "open_collector"))
      (node (ref "JP23") (pin "2") (pinfunction "2_2") (pintype "passive"))
    )
    (net (code "104") (name "3C3") (class "Default")
      (node (ref "IC11") (pin "9") (pinfunction "OUT2_9") (pintype "open_collector"))
      (node (ref "JP23") (pin "3") (pinfunction "3_3") (pintype "passive"))
    )
    (net (code "105") (name "3C4") (class "Default")
      (node (ref "IC11") (pin "10") (pinfunction "OUT3_10") (pintype "open_collector"))
      (node (ref "JP23") (pin "4") (pinfunction "4_4") (pintype "passive"))
    )
    (net (code "106") (name "3C5") (class "Default")
      (node (ref "IC11") (pin "11") (pinfunction "OUT4_11") (pintype "open_collector"))
      (node (ref "JP23") (pin "5") (pinfunction "5_5") (pintype "passive"))
    )
    (net (code "107") (name "3C6") (class "Default")
      (node (ref "IC11") (pin "12") (pinfunction "OUT5_12") (pintype "open_collector"))
      (node (ref "JP23") (pin "6") (pinfunction "6_6") (pintype "passive"))
    )
    (net (code "108") (name "3C7") (class "Default")
      (node (ref "IC11") (pin "13") (pinfunction "OUT6_13") (pintype "open_collector"))
      (node (ref "JP23") (pin "7") (pinfunction "7_7") (pintype "passive"))
    )
    (net (code "109") (name "3C8") (class "Default")
      (node (ref "IC11") (pin "14") (pinfunction "OUT7_14") (pintype "open_collector"))
      (node (ref "JP23") (pin "8") (pinfunction "8_8") (pintype "passive"))
    )
    (net (code "110") (name "3C9") (class "Default")
      (node (ref "IC11") (pin "15") (pinfunction "OUT8_15") (pintype "open_collector"))
      (node (ref "JP24") (pin "1") (pinfunction "1_1") (pintype "passive"))
    )
    (net (code "111") (name "3C10") (class "Default")
      (node (ref "IC11") (pin "16") (pinfunction "OUT9_16") (pintype "open_collector"))
      (node (ref "JP24") (pin "2") (pinfunction "2_2") (pintype "passive"))
    )
    (net (code "112") (name "3C11") (class "Default")
      (node (ref "IC11") (pin "17") (pinfunction "OUT10_17") (pintype "open_collector"))
      (node (ref "JP24") (pin "3") (pinfunction "3_3") (pintype "passive"))
    )
    (net (code "113") (name "3C12") (class "Default")
      (node (ref "IC11") (pin "18") (pinfunction "OUT11_18") (pintype "open_collector"))
      (node (ref "JP24") (pin "4") (pinfunction "4_4") (pintype "passive"))
    )
    (net (code "114") (name "3C13") (class "Default")
      (node (ref "IC11") (pin "19") (pinfunction "OUT12_19") (pintype "open_collector"))
      (node (ref "JP24") (pin "5") (pinfunction "5_5") (pintype "passive"))
    )
    (net (code "115") (name "3C14") (class "Default")
      (node (ref "IC11") (pin "20") (pinfunction "OUT13_20") (pintype "open_collector"))
      (node (ref "JP24") (pin "6") (pinfunction "6_6") (pintype "passive"))
    )
    (net (code "116") (name "3C15") (class "Default")
      (node (ref "IC11") (pin "21") (pinfunction "OUT14_21") (pintype "open_collector"))
      (node (ref "JP24") (pin "7") (pinfunction "7_7") (pintype "passive"))
    )
    (net (code "117") (name "3C16") (class "Default")
      (node (ref "IC11") (pin "22") (pinfunction "OUT15_22") (pintype "open_collector"))
      (node (ref "JP24") (pin "8") (pinfunction "8_8") (pintype "passive"))
    )
    (net (code "118") (name "3D1") (class "Default")
      (node (ref "IC12") (pin "7") (pinfunction "OUT0_7") (pintype "open_collector"))
      (node (ref "JP25") (pin "1") (pinfunction "1_1") (pintype "passive"))
    )
    (net (code "119") (name "3D2") (class "Default")
      (node (ref "IC12") (pin "8") (pinfunction "OUT1_8") (pintype "open_collector"))
      (node (ref "JP25") (pin "2") (pinfunction "2_2") (pintype "passive"))
    )
    (net (code "120") (name "3D3") (class "Default")
      (node (ref "IC12") (pin "9") (pinfunction "OUT2_9") (pintype "open_collector"))
      (node (ref "JP25") (pin "3") (pinfunction "3_3") (pintype "passive"))
    )
    (net (code "121") (name "3D4") (class "Default")
      (node (ref "IC12") (pin "10") (pinfunction "OUT3_10") (pintype "open_collector"))
      (node (ref "JP25") (pin "4") (pinfunction "4_4") (pintype "passive"))
    )
    (net (code "122") (name "3D5") (class "Default")
      (node (ref "IC12") (pin "11") (pinfunction "OUT4_11") (pintype "open_collector"))
      (node (ref "JP25") (pin "5") (pinfunction "5_5") (pintype "passive"))
    )
    (net (code "123") (name "3D6") (class "Default")
      (node (ref "IC12") (pin "12") (pinfunction "OUT5_12") (pintype "open_collector"))
      (node (ref "JP25") (pin "6") (pinfunction "6_6") (pintype "passive"))
    )
    (net (code "124") (name "3D7") (class "Default")
      (node (ref "IC12") (pin "13") (pinfunction "OUT6_13") (pintype "open_collector"))
      (node (ref "JP25") (pin "7") (pinfunction "7_7") (pintype "passive"))
    )
    (net (code "125") (name "3D8") (class "Default")
      (node (ref "IC12") (pin "14") (pinfunction "OUT7_14") (pintype "open_collector"))
      (node (ref "JP25") (pin "8") (pinfunction "8_8") (pintype "passive"))
    )
    (net (code "126") (name "3D9") (class "Default")
      (node (ref "IC12") (pin "15") (pinfunction "OUT8_15") (pintype "open_collector"))
      (node (ref "JP26") (pin "1") (pinfunction "1_1") (pintype "passive"))
    )
    (net (code "127") (name "3D10") (class "Default")
      (node (ref "IC12") (pin "16") (pinfunction "OUT9_16") (pintype "open_collector"))
      (node (ref "JP26") (pin "2") (pinfunction "2_2") (pintype "passive"))
    )
    (net (code "128") (name "3D11") (class "Default")
      (node (ref "IC12") (pin "17") (pinfunction "OUT10_17") (pintype "open_collector"))
      (node (ref "JP26") (pin "3") (pinfunction "3_3") (pintype "passive"))
    )
    (net (code "129") (name "3D12") (class "Default")
      (node (ref "IC12") (pin "18") (pinfunction "OUT11_18") (pintype "open_collector"))
      (node (ref "JP26") (pin "4") (pinfunction "4_4") (pintype "passive"))
    )
    (net (code "130") (name "3D13") (class "Default")
      (node (ref "IC12") (pin "19") (pinfunction "OUT12_19") (pintype "open_collector"))
      (node (ref "JP26") (pin "5") (pinfunction "5_5") (pintype "passive"))
    )
    (net (code "131") (name "3D14") (class "Default")
      (node (ref "IC12") (pin "20") (pinfunction "OUT13_20") (pintype "open_collector"))
      (node (ref "JP26") (pin "6") (pinfunction "6_6") (pintype "passive"))
    )
    (net (code "132") (name "3D15") (class "Default")
      (node (ref "IC12") (pin "21") (pinfunction "OUT14_21") (pintype "open_collector"))
      (node (ref "JP26") (pin "7") (pinfunction "7_7") (pintype "passive"))
    )
    (net (code "133") (name "3D16") (class "Default")
      (node (ref "IC12") (pin "22") (pinfunction "OUT15_22") (pintype "open_collector"))
      (node (ref "JP26") (pin "8") (pinfunction "8_8") (pintype "passive"))
    )
    (net (code "134") (name "3SIN") (class "Default")
      (node (ref "IC8") (pin "24") (pinfunction "SOUT_24") (pintype "output"))
      (node (ref "IC9") (pin "5") (pinfunction "SIN_5") (pintype "input"))
    )
    (net (code "135") (name "3SIN_B") (class "Default")
      (node (ref "IC10") (pin "5") (pinfunction "SIN_5") (pintype "input"))
      (node (ref "IC9") (pin "24") (pinfunction "SOUT_24") (pintype "output"))
    )
    (net (code "136") (name "3SIN_C") (class "Default")
      (node (ref "IC10") (pin "24") (pinfunction "SOUT_24") (pintype "output"))
      (node (ref "IC11") (pin "5") (pinfunction "SIN_5") (pintype "input"))
    )
    (net (code "137") (name "3SIN_D") (class "Default")
      (node (ref "IC11") (pin "24") (pinfunction "SOUT_24") (pintype "output"))
      (node (ref "IC12") (pin "5") (pinfunction "SIN_5") (pintype "input"))
    )
    (net (code "138") (name "4SIN") (class "Default")
      (node (ref "IC12") (pin "24") (pinfunction "SOUT_24") (pintype "output"))
    )
    (net (code "139") (name "A1") (class "Default")
      (node (ref "IC1") (pin "7") (pinfunction "OUT0_7") (pintype "open_collector"))
      (node (ref "JP2") (pin "1") (pinfunction "1_1") (pintype "passive"))
    )
    (net (code "140") (name "A2") (class "Default")
      (node (ref "IC1") (pin "8") (pinfunction "OUT1_8") (pintype "open_collector"))
      (node (ref "JP2") (pin "2") (pinfunction "2_2") (pintype "passive"))
    )
    (net (code "141") (name "A3") (class "Default")
      (node (ref "IC1") (pin "9") (pinfunction "OUT2_9") (pintype "open_collector"))
      (node (ref "JP2") (pin "3") (pinfunction "3_3") (pintype "passive"))
    )
    (net (code "142") (name "A4") (class "Default")
      (node (ref "IC1") (pin "10") (pinfunction "OUT3_10") (pintype "open_collector"))
      (node (ref "JP2") (pin "4") (pinfunction "4_4") (pintype "passive"))
    )
    (net (code "143") (name "A5") (class "Default")
      (node (ref "IC1") (pin "11") (pinfunction "OUT4_11") (pintype "open_collector"))
      (node (ref "JP2") (pin "5") (pinfunction "5_5") (pintype "passive"))
    )
    (net (code "144") (name "A6") (class "Default")
      (node (ref "IC1") (pin "12") (pinfunction "OUT5_12") (pintype "open_collector"))
      (node (ref "JP2") (pin "6") (pinfunction "6_6") (pintype "passive"))
    )
    (net (code "145") (name "A7") (class "Default")
      (node (ref "IC1") (pin "13") (pinfunction "OUT6_13") (pintype "open_collector"))
      (node (ref "JP2") (pin "7") (pinfunction "7_7") (pintype "passive"))
    )
    (net (code "146") (name "A8") (class "Default")
      (node (ref "IC1") (pin "14") (pinfunction "OUT7_14") (pintype "open_collector"))
      (node (ref "JP2") (pin "8") (pinfunction "8_8") (pintype "passive"))
    )
    (net (code "147") (name "A9") (class "Default")
      (node (ref "IC1") (pin "15") (pinfunction "OUT8_15") (pintype "open_collector"))
      (node (ref "JP3") (pin "1") (pinfunction "1_1") (pintype "passive"))
    )
    (net (code "148") (name "A10") (class "Default")
      (node (ref "IC1") (pin "16") (pinfunction "OUT9_16") (pintype "open_collector"))
      (node (ref "JP3") (pin "2") (pinfunction "2_2") (pintype "passive"))
    )
    (net (code "149") (name "A11") (class "Default")
      (node (ref "IC1") (pin "17") (pinfunction "OUT10_17") (pintype "open_collector"))
      (node (ref "JP3") (pin "3") (pinfunction "3_3") (pintype "passive"))
    )
    (net (code "150") (name "A12") (class "Default")
      (node (ref "IC1") (pin "18") (pinfunction "OUT11_18") (pintype "open_collector"))
      (node (ref "JP3") (pin "4") (pinfunction "4_4") (pintype "passive"))
    )
    (net (code "151") (name "A13") (class "Default")
      (node (ref "IC1") (pin "19") (pinfunction "OUT12_19") (pintype "open_collector"))
      (node (ref "JP3") (pin "5") (pinfunction "5_5") (pintype "passive"))
    )
    (net (code "152") (name "A14") (class "Default")
      (node (ref "IC1") (pin "20") (pinfunction "OUT13_20") (pintype "open_collector"))
      (node (ref "JP3") (pin "6") (pinfunction "6_6") (pintype "passive"))
    )
    (net (code "153") (name "A15") (class "Default")
      (node (ref "IC1") (pin "21") (pinfunction "OUT14_21") (pintype "open_collector"))
      (node (ref "JP3") (pin "7") (pinfunction "7_7") (pintype "passive"))
    )
    (net (code "154") (name "A16") (class "Default")
      (node (ref "IC1") (pin "22") (pinfunction "OUT15_22") (pintype "open_collector"))
      (node (ref "JP3") (pin "8") (pinfunction "8_8") (pintype "passive"))
    )
    (net (code "155") (name "B1") (class "Default")
      (node (ref "IC2") (pin "7") (pinfunction "OUT0_7") (pintype "open_collector"))
      (node (ref "JP4") (pin "1") (pinfunction "1_1") (pintype "passive"))
    )
    (net (code "156") (name "B2") (class "Default")
      (node (ref "IC2") (pin "8") (pinfunction "OUT1_8") (pintype "open_collector"))
      (node (ref "JP4") (pin "2") (pinfunction "2_2") (pintype "passive"))
    )
    (net (code "157") (name "B3") (class "Default")
      (node (ref "IC2") (pin "9") (pinfunction "OUT2_9") (pintype "open_collector"))
      (node (ref "JP4") (pin "3") (pinfunction "3_3") (pintype "passive"))
    )
    (net (code "158") (name "B4") (class "Default")
      (node (ref "IC2") (pin "10") (pinfunction "OUT3_10") (pintype "open_collector"))
      (node (ref "JP4") (pin "4") (pinfunction "4_4") (pintype "passive"))
    )
    (net (code "159") (name "B5") (class "Default")
      (node (ref "IC2") (pin "11") (pinfunction "OUT4_11") (pintype "open_collector"))
      (node (ref "JP4") (pin "5") (pinfunction "5_5") (pintype "passive"))
    )
    (net (code "160") (name "B6") (class "Default")
      (node (ref "IC2") (pin "12") (pinfunction "OUT5_12") (pintype "open_collector"))
      (node (ref "JP4") (pin "6") (pinfunction "6_6") (pintype "passive"))
    )
    (net (code "161") (name "B7") (class "Default")
      (node (ref "IC2") (pin "13") (pinfunction "OUT6_13") (pintype "open_collector"))
      (node (ref "JP4") (pin "7") (pinfunction "7_7") (pintype "passive"))
    )
    (net (code "162") (name "B8") (class "Default")
      (node (ref "IC2") (pin "14") (pinfunction "OUT7_14") (pintype "open_collector"))
      (node (ref "JP4") (pin "8") (pinfunction "8_8") (pintype "passive"))
    )
    (net (code "163") (name "B9") (class "Default")
      (node (ref "IC2") (pin "15") (pinfunction "OUT8_15") (pintype "open_collector"))
      (node (ref "JP5") (pin "1") (pinfunction "1_1") (pintype "passive"))
    )
    (net (code "164") (name "B10") (class "Default")
      (node (ref "IC2") (pin "16") (pinfunction "OUT9_16") (pintype "open_collector"))
      (node (ref "JP5") (pin "2") (pinfunction "2_2") (pintype "passive"))
    )
    (net (code "165") (name "B11") (class "Default")
      (node (ref "IC2") (pin "17") (pinfunction "OUT10_17") (pintype "open_collector"))
      (node (ref "JP5") (pin "3") (pinfunction "3_3") (pintype "passive"))
    )
    (net (code "166") (name "B12") (class "Default")
      (node (ref "IC2") (pin "18") (pinfunction "OUT11_18") (pintype "open_collector"))
      (node (ref "JP5") (pin "4") (pinfunction "4_4") (pintype "passive"))
    )
    (net (code "167") (name "B13") (class "Default")
      (node (ref "IC2") (pin "19") (pinfunction "OUT12_19") (pintype "open_collector"))
      (node (ref "JP5") (pin "5") (pinfunction "5_5") (pintype "passive"))
    )
    (net (code "168") (name "B14") (class "Default")
      (node (ref "IC2") (pin "20") (pinfunction "OUT13_20") (pintype "open_collector"))
      (node (ref "JP5") (pin "6") (pinfunction "6_6") (pintype "passive"))
    )
    (net (code "169") (name "B15") (class "Default")
      (node (ref "IC2") (pin "21") (pinfunction "OUT14_21") (pintype "open_collector"))
      (node (ref "JP5") (pin "7") (pinfunction "7_7") (pintype "passive"))
    )
    (net (code "170") (name "B16") (class "Default")
      (node (ref "IC2") (pin "22") (pinfunction "OUT15_22") (pintype "open_collector"))
      (node (ref "JP5") (pin "8") (pinfunction "8_8") (pintype "passive"))
    )
    (net (code "171") (name "BLANK") (class "Default")
      (node (ref "IC1") (pin "2") (pinfunction "BLANK_2") (pintype "input"))
      (node (ref "IC10") (pin "2") (pinfunction "BLANK_2") (pintype "input"))
      (node (ref "IC11") (pin "2") (pinfunction "BLANK_2") (pintype "input"))
      (node (ref "IC12") (pin "2") (pinfunction "BLANK_2") (pintype "input"))
      (node (ref "IC2") (pin "2") (pinfunction "BLANK_2") (pintype "input"))
      (node (ref "IC3") (pin "2") (pinfunction "BLANK_2") (pintype "input"))
      (node (ref "IC4") (pin "2") (pinfunction "BLANK_2") (pintype "input"))
      (node (ref "IC5") (pin "2") (pinfunction "BLANK_2") (pintype "input"))
      (node (ref "IC6") (pin "2") (pinfunction "BLANK_2") (pintype "input"))
      (node (ref "IC7") (pin "2") (pinfunction "BLANK_2") (pintype "input"))
      (node (ref "IC8") (pin "2") (pinfunction "BLANK_2") (pintype "input"))
      (node (ref "IC9") (pin "2") (pinfunction "BLANK_2") (pintype "input"))
      (node (ref "JP1") (pin "1") (pinfunction "1_1") (pintype "passive"))
      (node (ref "LPC1") (pin "24") (pinfunction "24_24") (pintype "passive"))
    )
    (net (code "172") (name "C1") (class "Default")
      (node (ref "IC3") (pin "7") (pinfunction "OUT0_7") (pintype "open_collector"))
      (node (ref "JP7") (pin "1") (pinfunction "1_1") (pintype "passive"))
    )
    (net (code "173") (name "C2") (class "Default")
      (node (ref "IC3") (pin "8") (pinfunction "OUT1_8") (pintype "open_collector"))
      (node (ref "JP7") (pin "2") (pinfunction "2_2") (pintype "passive"))
    )
    (net (code "174") (name "C3") (class "Default")
      (node (ref "IC3") (pin "9") (pinfunction "OUT2_9") (pintype "open_collector"))
      (node (ref "JP7") (pin "3") (pinfunction "3_3") (pintype "passive"))
    )
    (net (code "175") (name "C4") (class "Default")
      (node (ref "IC3") (pin "10") (pinfunction "OUT3_10") (pintype "open_collector"))
      (node (ref "JP7") (pin "4") (pinfunction "4_4") (pintype "passive"))
    )
    (net (code "176") (name "C5") (class "Default")
      (node (ref "IC3") (pin "11") (pinfunction "OUT4_11") (pintype "open_collector"))
      (node (ref "JP7") (pin "5") (pinfunction "5_5") (pintype "passive"))
    )
    (net (code "177") (name "C6") (class "Default")
      (node (ref "IC3") (pin "12") (pinfunction "OUT5_12") (pintype "open_collector"))
      (node (ref "JP7") (pin "6") (pinfunction "6_6") (pintype "passive"))
    )
    (net (code "178") (name "C7") (class "Default")
      (node (ref "IC3") (pin "13") (pinfunction "OUT6_13") (pintype "open_collector"))
      (node (ref "JP7") (pin "7") (pinfunction "7_7") (pintype "passive"))
    )
    (net (code "179") (name "C8") (class "Default")
      (node (ref "IC3") (pin "14") (pinfunction "OUT7_14") (pintype "open_collector"))
      (node (ref "JP7") (pin "8") (pinfunction "8_8") (pintype "passive"))
    )
    (net (code "180") (name "C9") (class "Default")
      (node (ref "IC3") (pin "15") (pinfunction "OUT8_15") (pintype "open_collector"))
      (node (ref "JP8") (pin "1") (pinfunction "1_1") (pintype "passive"))
    )
    (net (code "181") (name "C10") (class "Default")
      (node (ref "IC3") (pin "16") (pinfunction "OUT9_16") (pintype "open_collector"))
      (node (ref "JP8") (pin "2") (pinfunction "2_2") (pintype "passive"))
    )
    (net (code "182") (name "C11") (class "Default")
      (node (ref "IC3") (pin "17") (pinfunction "OUT10_17") (pintype "open_collector"))
      (node (ref "JP8") (pin "3") (pinfunction "3_3") (pintype "passive"))
    )
    (net (code "183") (name "C12") (class "Default")
      (node (ref "IC3") (pin "18") (pinfunction "OUT11_18") (pintype "open_collector"))
      (node (ref "JP8") (pin "4") (pinfunction "4_4") (pintype "passive"))
    )
    (net (code "184") (name "C13") (class "Default")
      (node (ref "IC3") (pin "19") (pinfunction "OUT12_19") (pintype "open_collector"))
      (node (ref "JP8") (pin "5") (pinfunction "5_5") (pintype "passive"))
    )
    (net (code "185") (name "C14") (class "Default")
      (node (ref "IC3") (pin "20") (pinfunction "OUT13_20") (pintype "open_collector"))
      (node (ref "JP8") (pin "6") (pinfunction "6_6") (pintype "passive"))
    )
    (net (code "186") (name "C15") (class "Default")
      (node (ref "IC3") (pin "21") (pinfunction "OUT14_21") (pintype "open_collector"))
      (node (ref "JP8") (pin "7") (pinfunction "7_7") (pintype "passive"))
    )
    (net (code "187") (name "C16") (class "Default")
      (node (ref "IC3") (pin "22") (pinfunction "OUT15_22") (pintype "open_collector"))
      (node (ref "JP8") (pin "8") (pinfunction "8_8") (pintype "passive"))
    )
    (net (code "188") (name "D1") (class "Default")
      (node (ref "IC4") (pin "7") (pinfunction "OUT0_7") (pintype "open_collector"))
      (node (ref "JP9") (pin "1") (pinfunction "1_1") (pintype "passive"))
    )
    (net (code "189") (name "D2") (class "Default")
      (node (ref "IC4") (pin "8") (pinfunction "OUT1_8") (pintype "open_collector"))
      (node (ref "JP9") (pin "2") (pinfunction "2_2") (pintype "passive"))
    )
    (net (code "190") (name "D3") (class "Default")
      (node (ref "IC4") (pin "9") (pinfunction "OUT2_9") (pintype "open_collector"))
      (node (ref "JP9") (pin "3") (pinfunction "3_3") (pintype "passive"))
    )
    (net (code "191") (name "D4") (class "Default")
      (node (ref "IC4") (pin "10") (pinfunction "OUT3_10") (pintype "open_collector"))
      (node (ref "JP9") (pin "4") (pinfunction "4_4") (pintype "passive"))
    )
    (net (code "192") (name "D5") (class "Default")
      (node (ref "IC4") (pin "11") (pinfunction "OUT4_11") (pintype "open_collector"))
      (node (ref "JP9") (pin "5") (pinfunction "5_5") (pintype "passive"))
    )
    (net (code "193") (name "D6") (class "Default")
      (node (ref "IC4") (pin "12") (pinfunction "OUT5_12") (pintype "open_collector"))
      (node (ref "JP9") (pin "6") (pinfunction "6_6") (pintype "passive"))
    )
    (net (code "194") (name "D7") (class "Default")
      (node (ref "IC4") (pin "13") (pinfunction "OUT6_13") (pintype "open_collector"))
      (node (ref "JP9") (pin "7") (pinfunction "7_7") (pintype "passive"))
    )
    (net (code "195") (name "D8") (class "Default")
      (node (ref "IC4") (pin "14") (pinfunction "OUT7_14") (pintype "open_collector"))
      (node (ref "JP9") (pin "8") (pinfunction "8_8") (pintype "passive"))
    )
    (net (code "196") (name "D9") (class "Default")
      (node (ref "IC4") (pin "15") (pinfunction "OUT8_15") (pintype "open_collector"))
      (node (ref "JP10") (pin "1") (pinfunction "1_1") (pintype "passive"))
    )
    (net (code "197") (name "D10") (class "Default")
      (node (ref "IC4") (pin "16") (pinfunction "OUT9_16") (pintype "open_collector"))
      (node (ref "JP10") (pin "2") (pinfunction "2_2") (pintype "passive"))
    )
    (net (code "198") (name "D11") (class "Default")
      (node (ref "IC4") (pin "17") (pinfunction "OUT10_17") (pintype "open_collector"))
      (node (ref "JP10") (pin "3") (pinfunction "3_3") (pintype "passive"))
    )
    (net (code "199") (name "D12") (class "Default")
      (node (ref "IC4") (pin "18") (pinfunction "OUT11_18") (pintype "open_collector"))
      (node (ref "JP10") (pin "4") (pinfunction "4_4") (pintype "passive"))
    )
    (net (code "200") (name "D13") (class "Default")
      (node (ref "IC4") (pin "19") (pinfunction "OUT12_19") (pintype "open_collector"))
      (node (ref "JP10") (pin "5") (pinfunction "5_5") (pintype "passive"))
    )
    (net (code "201") (name "D14") (class "Default")
      (node (ref "IC4") (pin "20") (pinfunction "OUT13_20") (pintype "open_collector"))
      (node (ref "JP10") (pin "6") (pinfunction "6_6") (pintype "passive"))
    )
    (net (code "202") (name "D15") (class "Default")
      (node (ref "IC4") (pin "21") (pinfunction "OUT14_21") (pintype "open_collector"))
      (node (ref "JP10") (pin "7") (pinfunction "7_7") (pintype "passive"))
    )
    (net (code "203") (name "D16") (class "Default")
      (node (ref "IC4") (pin "22") (pinfunction "OUT15_22") (pintype "open_collector"))
      (node (ref "JP10") (pin "8") (pinfunction "8_8") (pintype "passive"))
    )
    (net (code "204") (name "DCPRG") (class "Default")
      (node (ref "IC1") (pin "26") (pinfunction "DCPRG_26") (pintype "input"))
      (node (ref "IC10") (pin "26") (pinfunction "DCPRG_26") (pintype "input"))
      (node (ref "IC11") (pin "26") (pinfunction "DCPRG_26") (pintype "input"))
      (node (ref "IC12") (pin "26") (pinfunction "DCPRG_26") (pintype "input"))
      (node (ref "IC2") (pin "26") (pinfunction "DCPRG_26") (pintype "input"))
      (node (ref "IC3") (pin "26") (pinfunction "DCPRG_26") (pintype "input"))
      (node (ref "IC4") (pin "26") (pinfunction "DCPRG_26") (pintype "input"))
      (node (ref "IC5") (pin "26") (pinfunction "DCPRG_26") (pintype "input"))
      (node (ref "IC6") (pin "26") (pinfunction "DCPRG_26") (pintype "input"))
      (node (ref "IC7") (pin "26") (pinfunction "DCPRG_26") (pintype "input"))
      (node (ref "IC8") (pin "26") (pinfunction "DCPRG_26") (pintype "input"))
      (node (ref "IC9") (pin "26") (pinfunction "DCPRG_26") (pintype "input"))
      (node (ref "JP1") (pin "9") (pinfunction "9_9") (pintype "passive"))
      (node (ref "LPC1") (pin "26") (pinfunction "26_26") (pintype "passive"))
    )
    (net (code "205") (name "GND") (class "Default")
      (node (ref "C1") (pin "1") (pinfunction "1_1") (pintype "passive"))
      (node (ref "C10") (pin "1") (pinfunction "1_1") (pintype "passive"))
      (node (ref "C11") (pin "1") (pinfunction "1_1") (pintype "passive"))
      (node (ref "C12") (pin "1") (pinfunction "1_1") (pintype "passive"))
      (node (ref "C2") (pin "1") (pinfunction "1_1") (pintype "passive"))
      (node (ref "C3") (pin "1") (pinfunction "1_1") (pintype "passive"))
      (node (ref "C4") (pin "1") (pinfunction "1_1") (pintype "passive"))
      (node (ref "C5") (pin "1") (pinfunction "1_1") (pintype "passive"))
      (node (ref "C6") (pin "1") (pinfunction "1_1") (pintype "passive"))
      (node (ref "C7") (pin "1") (pinfunction "1_1") (pintype "passive"))
      (node (ref "C8") (pin "1") (pinfunction "1_1") (pintype "passive"))
      (node (ref "C9") (pin "1") (pinfunction "1_1") (pintype "passive"))
      (node (ref "IC1") (pin "1") (pinfunction "GND_1") (pintype "power_in"))
      (node (ref "IC10") (pin "1") (pinfunction "GND_1") (pintype "power_in"))
      (node (ref "IC11") (pin "1") (pinfunction "GND_1") (pintype "power_in"))
      (node (ref "IC12") (pin "1") (pinfunction "GND_1") (pintype "power_in"))
      (node (ref "IC2") (pin "1") (pinfunction "GND_1") (pintype "power_in"))
      (node (ref "IC3") (pin "1") (pinfunction "GND_1") (pintype "power_in"))
      (node (ref "IC4") (pin "1") (pinfunction "GND_1") (pintype "power_in"))
      (node (ref "IC5") (pin "1") (pinfunction "GND_1") (pintype "power_in"))
      (node (ref "IC6") (pin "1") (pinfunction "GND_1") (pintype "power_in"))
      (node (ref "IC7") (pin "1") (pinfunction "GND_1") (pintype "power_in"))
      (node (ref "IC8") (pin "1") (pinfunction "GND_1") (pintype "power_in"))
      (node (ref "IC9") (pin "1") (pinfunction "GND_1") (pintype "power_in"))
      (node (ref "JP1") (pin "4") (pinfunction "4_4") (pintype "passive"))
      (node (ref "JP27") (pin "1") (pinfunction "1_1") (pintype "passive"))
      (node (ref "LPC1") (pin "1") (pinfunction "1_1") (pintype "passive"))
      (node (ref "PAD1") (pin "1") (pinfunction "P_1") (pintype "passive"))
      (node (ref "PAD3") (pin "1") (pinfunction "P_1") (pintype "passive"))
      (node (ref "R1") (pin "2") (pinfunction "2_2") (pintype "passive"))
      (node (ref "R10") (pin "2") (pinfunction "2_2") (pintype "passive"))
      (node (ref "R11") (pin "2") (pinfunction "2_2") (pintype "passive"))
      (node (ref "R12") (pin "2") (pinfunction "2_2") (pintype "passive"))
      (node (ref "R13") (pin "1") (pinfunction "1_1") (pintype "passive"))
      (node (ref "R14") (pin "1") (pinfunction "1_1") (pintype "passive"))
      (node (ref "R15") (pin "1") (pinfunction "1_1") (pintype "passive"))
      (node (ref "R16") (pin "1") (pinfunction "1_1") (pintype "passive"))
      (node (ref "R17") (pin "1") (pinfunction "1_1") (pintype "passive"))
      (node (ref "R18") (pin "1") (pinfunction "1_1") (pintype "passive"))
      (node (ref "R19") (pin "1") (pinfunction "1_1") (pintype "passive"))
      (node (ref "R2") (pin "2") (pinfunction "2_2") (pintype "passive"))
      (node (ref "R20") (pin "1") (pinfunction "1_1") (pintype "passive"))
      (node (ref "R21") (pin "1") (pinfunction "1_1") (pintype "passive"))
      (node (ref "R3") (pin "2") (pinfunction "2_2") (pintype "passive"))
      (node (ref "R4") (pin "2") (pinfunction "2_2") (pintype "passive"))
      (node (ref "R5") (pin "2") (pinfunction "2_2") (pintype "passive"))
      (node (ref "R6") (pin "2") (pinfunction "2_2") (pintype "passive"))
      (node (ref "R7") (pin "2") (pinfunction "2_2") (pintype "passive"))
      (node (ref "R8") (pin "2") (pinfunction "2_2") (pintype "passive"))
      (node (ref "R9") (pin "2") (pinfunction "2_2") (pintype "passive"))
      (node (ref "SV1") (pin "3") (pinfunction "3_3") (pintype "passive"))
      (node (ref "SV2") (pin "3") (pinfunction "3_3") (pintype "passive"))
    )
    (net (code "206") (name "GND_IN") (class "Default")
      (node (ref "J1") (pin "2") (pinfunction "2_2") (pintype "passive"))
      (node (ref "J1") (pin "3") (pinfunction "3_3") (pintype "passive"))
      (node (ref "JP27") (pin "2") (pinfunction "2_2") (pintype "passive"))
    )
    (net (code "207") (name "GSCLK") (class "Default")
      (node (ref "IC1") (pin "25") (pinfunction "GSCLK_25") (pintype "input"))
      (node (ref "IC10") (pin "25") (pinfunction "GSCLK_25") (pintype "input"))
      (node (ref "IC11") (pin "25") (pinfunction "GSCLK_25") (pintype "input"))
      (node (ref "IC12") (pin "25") (pinfunction "GSCLK_25") (pintype "input"))
      (node (ref "IC2") (pin "25") (pinfunction "GSCLK_25") (pintype "input"))
      (node (ref "IC3") (pin "25") (pinfunction "GSCLK_25") (pintype "input"))
      (node (ref "IC4") (pin "25") (pinfunction "GSCLK_25") (pintype "input"))
      (node (ref "IC5") (pin "25") (pinfunction "GSCLK_25") (pintype "input"))
      (node (ref "IC6") (pin "25") (pinfunction "GSCLK_25") (pintype "input"))
      (node (ref "IC7") (pin "25") (pinfunction "GSCLK_25") (pintype "input"))
      (node (ref "IC8") (pin "25") (pinfunction "GSCLK_25") (pintype "input"))
      (node (ref "IC9") (pin "25") (pinfunction "GSCLK_25") (pintype "input"))
      (node (ref "JP1") (pin "2") (pinfunction "2_2") (pintype "passive"))
      (node (ref "LPC1") (pin "42") (pinfunction "42_42") (pintype "passive"))
    )
    (net (code "208") (name "L1") (class "Default")
      (node (ref "JP6") (pin "1") (pinfunction "1_1") (pintype "passive"))
      (node (ref "Q1") (pin "2") (pinfunction "D_2") (pintype "passive"))
      (node (ref "R14") (pin "2") (pinfunction "2_2") (pintype "passive"))
    )
    (net (code "209") (name "L2") (class "Default")
      (node (ref "JP6") (pin "2") (pinfunction "2_2") (pintype "passive"))
      (node (ref "Q3") (pin "2") (pinfunction "D_2") (pintype "passive"))
      (node (ref "R16") (pin "2") (pinfunction "2_2") (pintype "passive"))
    )
    (net (code "210") (name "L3") (class "Default")
      (node (ref "JP6") (pin "3") (pinfunction "3_3") (pintype "passive"))
      (node (ref "Q5") (pin "2") (pinfunction "D_2") (pintype "passive"))
      (node (ref "R18") (pin "2") (pinfunction "2_2") (pintype "passive"))
    )
    (net (code "211") (name "L4") (class "Default")
      (node (ref "JP6") (pin "4") (pinfunction "4_4") (pintype "passive"))
      (node (ref "Q7") (pin "2") (pinfunction "D_2") (pintype "passive"))
      (node (ref "R20") (pin "2") (pinfunction "2_2") (pintype "passive"))
    )
    (net (code "212") (name "L5") (class "Default")
      (node (ref "JP6") (pin "5") (pinfunction "5_5") (pintype "passive"))
      (node (ref "Q2") (pin "2") (pinfunction "D_2") (pintype "passive"))
      (node (ref "R15") (pin "2") (pinfunction "2_2") (pintype "passive"))
    )
    (net (code "213") (name "L6") (class "Default")
      (node (ref "JP6") (pin "6") (pinfunction "6_6") (pintype "passive"))
      (node (ref "Q4") (pin "2") (pinfunction "D_2") (pintype "passive"))
      (node (ref "R17") (pin "2") (pinfunction "2_2") (pintype "passive"))
    )
    (net (code "214") (name "L7") (class "Default")
      (node (ref "JP6") (pin "7") (pinfunction "7_7") (pintype "passive"))
      (node (ref "Q6") (pin "2") (pinfunction "D_2") (pintype "passive"))
      (node (ref "R19") (pin "2") (pinfunction "2_2") (pintype "passive"))
    )
    (net (code "215") (name "L8") (class "Default")
      (node (ref "JP6") (pin "8") (pinfunction "8_8") (pintype "passive"))
      (node (ref "Q8") (pin "2") (pinfunction "D_2") (pintype "passive"))
      (node (ref "R21") (pin "2") (pinfunction "2_2") (pintype "passive"))
    )
    (net (code "216") (name "LAYER1") (class "Default")
      (node (ref "LPC1") (pin "73") (pinfunction "73_73") (pintype "passive"))
      (node (ref "Q1") (pin "1") (pinfunction "G_1") (pintype "passive"))
    )
    (net (code "217") (name "LAYER2") (class "Default")
      (node (ref "LPC1") (pin "72") (pinfunction "72_72") (pintype "passive"))
      (node (ref "Q3") (pin "1") (pinfunction "G_1") (pintype "passive"))
    )
    (net (code "218") (name "LAYER3") (class "Default")
      (node (ref "LPC1") (pin "71") (pinfunction "71_71") (pintype "passive"))
      (node (ref "Q5") (pin "1") (pinfunction "G_1") (pintype "passive"))
    )
    (net (code "219") (name "LAYER4") (class "Default")
      (node (ref "LPC1") (pin "70") (pinfunction "70_70") (pintype "passive"))
      (node (ref "Q7") (pin "1") (pinfunction "G_1") (pintype "passive"))
    )
    (net (code "220") (name "LAYER5") (class "Default")
      (node (ref "LPC1") (pin "69") (pinfunction "69_69") (pintype "passive"))
      (node (ref "Q2") (pin "1") (pinfunction "G_1") (pintype "passive"))
    )
    (net (code "221") (name "LAYER6") (class "Default")
      (node (ref "LPC1") (pin "68") (pinfunction "68_68") (pintype "passive"))
      (node (ref "Q4") (pin "1") (pinfunction "G_1") (pintype "passive"))
    )
    (net (code "222") (name "LAYER7") (class "Default")
      (node (ref "LPC1") (pin "67") (pinfunction "67_67") (pintype "passive"))
      (node (ref "Q6") (pin "1") (pinfunction "G_1") (pintype "passive"))
    )
    (net (code "223") (name "LAYER8") (class "Default")
      (node (ref "LPC1") (pin "66") (pinfunction "66_66") (pintype "passive"))
      (node (ref "Q8") (pin "1") (pinfunction "G_1") (pintype "passive"))
    )
    (net (code "224") (name "Net-(IC1-IREF)") (class "Default")
      (node (ref "IC1") (pin "27") (pinfunction "IREF_27") (pintype "passive"))
      (node (ref "R1") (pin "1") (pinfunction "1_1") (pintype "passive"))
    )
    (net (code "225") (name "Net-(IC2-IREF)") (class "Default")
      (node (ref "IC2") (pin "27") (pinfunction "IREF_27") (pintype "passive"))
      (node (ref "R2") (pin "1") (pinfunction "1_1") (pintype "passive"))
    )
    (net (code "226") (name "Net-(IC3-IREF)") (class "Default")
      (node (ref "IC3") (pin "27") (pinfunction "IREF_27") (pintype "passive"))
      (node (ref "R3") (pin "1") (pinfunction "1_1") (pintype "passive"))
    )
    (net (code "227") (name "Net-(IC4-IREF)") (class "Default")
      (node (ref "IC4") (pin "27") (pinfunction "IREF_27") (pintype "passive"))
      (node (ref "R4") (pin "1") (pinfunction "1_1") (pintype "passive"))
    )
    (net (code "228") (name "Net-(IC5-IREF)") (class "Default")
      (node (ref "IC5") (pin "27") (pinfunction "IREF_27") (pintype "passive"))
      (node (ref "R5") (pin "1") (pinfunction "1_1") (pintype "passive"))
    )
    (net (code "229") (name "Net-(IC6-IREF)") (class "Default")
      (node (ref "IC6") (pin "27") (pinfunction "IREF_27") (pintype "passive"))
      (node (ref "R6") (pin "1") (pinfunction "1_1") (pintype "passive"))
    )
    (net (code "230") (name "Net-(IC7-IREF)") (class "Default")
      (node (ref "IC7") (pin "27") (pinfunction "IREF_27") (pintype "passive"))
      (node (ref "R7") (pin "1") (pinfunction "1_1") (pintype "passive"))
    )
    (net (code "231") (name "Net-(IC8-IREF)") (class "Default")
      (node (ref "IC8") (pin "27") (pinfunction "IREF_27") (pintype "passive"))
      (node (ref "R8") (pin "1") (pinfunction "1_1") (pintype "passive"))
    )
    (net (code "232") (name "Net-(IC9-IREF)") (class "Default")
      (node (ref "IC9") (pin "27") (pinfunction "IREF_27") (pintype "passive"))
      (node (ref "R9") (pin "1") (pinfunction "1_1") (pintype "passive"))
    )
    (net (code "233") (name "Net-(IC10-IREF)") (class "Default")
      (node (ref "IC10") (pin "27") (pinfunction "IREF_27") (pintype "passive"))
      (node (ref "R10") (pin "1") (pinfunction "1_1") (pintype "passive"))
    )
    (net (code "234") (name "Net-(IC11-IREF)") (class "Default")
      (node (ref "IC11") (pin "27") (pinfunction "IREF_27") (pintype "passive"))
      (node (ref "R11") (pin "1") (pinfunction "1_1") (pintype "passive"))
    )
    (net (code "235") (name "Net-(IC12-IREF)") (class "Default")
      (node (ref "IC12") (pin "27") (pinfunction "IREF_27") (pintype "passive"))
      (node (ref "R12") (pin "1") (pinfunction "1_1") (pintype "passive"))
    )
    (net (code "236") (name "RESET_N") (class "Default")
      (node (ref "C13") (pin "2") (pinfunction "2_2") (pintype "passive"))
      (node (ref "LPC1") (pin "4") (pinfunction "4_4") (pintype "passive"))
      (node (ref "R13") (pin "2") (pinfunction "2_2") (pintype "passive"))
      (node (ref "S1") (pin "4") (pinfunction "P1_4") (pintype "passive"))
    )
    (net (code "237") (name "RX2") (class "Default")
      (node (ref "LPC1") (pin "41") (pinfunction "41_41") (pintype "passive"))
      (node (ref "SV1") (pin "2") (pinfunction "2_2") (pintype "passive"))
    )
    (net (code "238") (name "RX3") (class "Default")
      (node (ref "LPC1") (pin "10") (pinfunction "10_10") (pintype "passive"))
      (node (ref "SV2") (pin "2") (pinfunction "2_2") (pintype "passive"))
    )
    (net (code "239") (name "SCLK") (class "Default")
      (node (ref "IC1") (pin "4") (pinfunction "SCLK_4") (pintype "input"))
      (node (ref "IC10") (pin "4") (pinfunction "SCLK_4") (pintype "input"))
      (node (ref "IC11") (pin "4") (pinfunction "SCLK_4") (pintype "input"))
      (node (ref "IC12") (pin "4") (pinfunction "SCLK_4") (pintype "input"))
      (node (ref "IC2") (pin "4") (pinfunction "SCLK_4") (pintype "input"))
      (node (ref "IC3") (pin "4") (pinfunction "SCLK_4") (pintype "input"))
      (node (ref "IC4") (pin "4") (pinfunction "SCLK_4") (pintype "input"))
      (node (ref "IC5") (pin "4") (pinfunction "SCLK_4") (pintype "input"))
      (node (ref "IC6") (pin "4") (pinfunction "SCLK_4") (pintype "input"))
      (node (ref "IC7") (pin "4") (pinfunction "SCLK_4") (pintype "input"))
      (node (ref "IC8") (pin "4") (pinfunction "SCLK_4") (pintype "input"))
      (node (ref "IC9") (pin "4") (pinfunction "SCLK_4") (pintype "input"))
      (node (ref "JP1") (pin "3") (pinfunction "3_3") (pintype "passive"))
      (node (ref "LPC1") (pin "11") (pinfunction "11_11") (pintype "passive"))
    )
    (net (code "240") (name "SIN") (class "Default")
      (node (ref "IC1") (pin "5") (pinfunction "SIN_5") (pintype "input"))
      (node (ref "JP1") (pin "5") (pinfunction "5_5") (pintype "passive"))
      (node (ref "LPC1") (pin "13") (pinfunction "13_13") (pintype "passive"))
    )
    (net (code "241") (name "SIN_B") (class "Default")
      (node (ref "IC1") (pin "24") (pinfunction "SOUT_24") (pintype "output"))
      (node (ref "IC2") (pin "5") (pinfunction "SIN_5") (pintype "input"))
    )
    (net (code "242") (name "SIN_C") (class "Default")
      (node (ref "IC2") (pin "24") (pinfunction "SOUT_24") (pintype "output"))
      (node (ref "IC3") (pin "5") (pinfunction "SIN_5") (pintype "input"))
    )
    (net (code "243") (name "SIN_D") (class "Default")
      (node (ref "IC3") (pin "24") (pinfunction "SOUT_24") (pintype "output"))
      (node (ref "IC4") (pin "5") (pinfunction "SIN_5") (pintype "input"))
    )
    (net (code "244") (name "TX2") (class "Default")
      (node (ref "LPC1") (pin "40") (pinfunction "40_40") (pintype "passive"))
      (node (ref "SV1") (pin "1") (pinfunction "1_1") (pintype "passive"))
    )
    (net (code "245") (name "TX3") (class "Default")
      (node (ref "LPC1") (pin "9") (pinfunction "9_9") (pintype "passive"))
      (node (ref "SV2") (pin "1") (pinfunction "1_1") (pintype "passive"))
    )
    (net (code "246") (name "V3_IN") (class "Default")
      (node (ref "JP27") (pin "4") (pinfunction "4_4") (pintype "passive"))
      (node (ref "PAD2") (pin "1") (pinfunction "P_1") (pintype "passive"))
    )
    (net (code "247") (name "V5+") (class "Default")
      (node (ref "JP27") (pin "5") (pinfunction "5_5") (pintype "passive"))
      (node (ref "LPC1") (pin "2") (pinfunction "2_2") (pintype "passive"))
      (node (ref "SV1") (pin "4") (pinfunction "4_4") (pintype "passive"))
      (node (ref "SV2") (pin "4") (pinfunction "4_4") (pintype "passive"))
    )
    (net (code "248") (name "V5_IN") (class "Default")
      (node (ref "J1") (pin "1") (pinfunction "1_1") (pintype "passive"))
      (node (ref "JP27") (pin "6") (pinfunction "6_6") (pintype "passive"))
      (node (ref "PAD4") (pin "1") (pinfunction "P_1") (pintype "passive"))
    )
    (net (code "249") (name "VCC") (class "Default")
      (node (ref "C1") (pin "2") (pinfunction "2_2") (pintype "passive"))
      (node (ref "C10") (pin "2") (pinfunction "2_2") (pintype "passive"))
      (node (ref "C11") (pin "2") (pinfunction "2_2") (pintype "passive"))
      (node (ref "C12") (pin "2") (pinfunction "2_2") (pintype "passive"))
      (node (ref "C2") (pin "2") (pinfunction "2_2") (pintype "passive"))
      (node (ref "C3") (pin "2") (pinfunction "2_2") (pintype "passive"))
      (node (ref "C4") (pin "2") (pinfunction "2_2") (pintype "passive"))
      (node (ref "C5") (pin "2") (pinfunction "2_2") (pintype "passive"))
      (node (ref "C6") (pin "2") (pinfunction "2_2") (pintype "passive"))
      (node (ref "C7") (pin "2") (pinfunction "2_2") (pintype "passive"))
      (node (ref "C8") (pin "2") (pinfunction "2_2") (pintype "passive"))
      (node (ref "C9") (pin "2") (pinfunction "2_2") (pintype "passive"))
      (node (ref "IC1") (pin "28") (pinfunction "VCC_28") (pintype "power_in"))
      (node (ref "IC10") (pin "28") (pinfunction "VCC_28") (pintype "power_in"))
      (node (ref "IC11") (pin "28") (pinfunction "VCC_28") (pintype "power_in"))
      (node (ref "IC12") (pin "28") (pinfunction "VCC_28") (pintype "power_in"))
      (node (ref "IC2") (pin "28") (pinfunction "VCC_28") (pintype "power_in"))
      (node (ref "IC3") (pin "28") (pinfunction "VCC_28") (pintype "power_in"))
      (node (ref "IC4") (pin "28") (pinfunction "VCC_28") (pintype "power_in"))
      (node (ref "IC5") (pin "28") (pinfunction "VCC_28") (pintype "power_in"))
      (node (ref "IC6") (pin "28") (pinfunction "VCC_28") (pintype "power_in"))
      (node (ref "IC7") (pin "28") (pinfunction "VCC_28") (pintype "power_in"))
      (node (ref "IC8") (pin "28") (pinfunction "VCC_28") (pintype "power_in"))
      (node (ref "IC9") (pin "28") (pinfunction "VCC_28") (pintype "power_in"))
      (node (ref "JP1") (pin "6") (pinfunction "6_6") (pintype "passive"))
      (node (ref "JP27") (pin "3") (pinfunction "3_3") (pintype "passive"))
      (node (ref "Q1") (pin "3") (pinfunction "S_3") (pintype "passive"))
      (node (ref "Q2") (pin "3") (pinfunction "S_3") (pintype "passive"))
      (node (ref "Q3") (pin "3") (pinfunction "S_3") (pintype "passive"))
      (node (ref "Q4") (pin "3") (pinfunction "S_3") (pintype "passive"))
      (node (ref "Q5") (pin "3") (pinfunction "S_3") (pintype "passive"))
      (node (ref "Q6") (pin "3") (pinfunction "S_3") (pintype "passive"))
      (node (ref "Q7") (pin "3") (pinfunction "S_3") (pintype "passive"))
      (node (ref "Q8") (pin "3") (pinfunction "S_3") (pintype "passive"))
    )
    (net (code "250") (name "VPRG") (class "Default")
      (node (ref "IC1") (pin "6") (pinfunction "VPRG_6") (pintype "input"))
      (node (ref "IC10") (pin "6") (pinfunction "VPRG_6") (pintype "input"))
      (node (ref "IC11") (pin "6") (pinfunction "VPRG_6") (pintype "input"))
      (node (ref "IC12") (pin "6") (pinfunction "VPRG_6") (pintype "input"))
      (node (ref "IC2") (pin "6") (pinfunction "VPRG_6") (pintype "input"))
      (node (ref "IC3") (pin "6") (pinfunction "VPRG_6") (pintype "input"))
      (node (ref "IC4") (pin "6") (pinfunction "VPRG_6") (pintype "input"))
      (node (ref "IC5") (pin "6") (pinfunction "VPRG_6") (pintype "input"))
      (node (ref "IC6") (pin "6") (pinfunction "VPRG_6") (pintype "input"))
      (node (ref "IC7") (pin "6") (pinfunction "VPRG_6") (pintype "input"))
      (node (ref "IC8") (pin "6") (pinfunction "VPRG_6") (pintype "input"))
      (node (ref "IC9") (pin "6") (pinfunction "VPRG_6") (pintype "input"))
      (node (ref "JP1") (pin "10") (pinfunction "10_10") (pintype "passive"))
      (node (ref "LPC1") (pin "25") (pinfunction "25_25") (pintype "passive"))
    )
    (net (code "251") (name "XLAT") (class "Default")
      (node (ref "IC1") (pin "3") (pinfunction "XLAT_3") (pintype "input"))
      (node (ref "IC10") (pin "3") (pinfunction "XLAT_3") (pintype "input"))
      (node (ref "IC11") (pin "3") (pinfunction "XLAT_3") (pintype "input"))
      (node (ref "IC12") (pin "3") (pinfunction "XLAT_3") (pintype "input"))
      (node (ref "IC2") (pin "3") (pinfunction "XLAT_3") (pintype "input"))
      (node (ref "IC3") (pin "3") (pinfunction "XLAT_3") (pintype "input"))
      (node (ref "IC4") (pin "3") (pinfunction "XLAT_3") (pintype "input"))
      (node (ref "IC5") (pin "3") (pinfunction "XLAT_3") (pintype "input"))
      (node (ref "IC6") (pin "3") (pinfunction "XLAT_3") (pintype "input"))
      (node (ref "IC7") (pin "3") (pinfunction "XLAT_3") (pintype "input"))
      (node (ref "IC8") (pin "3") (pinfunction "XLAT_3") (pintype "input"))
      (node (ref "IC9") (pin "3") (pinfunction "XLAT_3") (pintype "input"))
      (node (ref "JP1") (pin "7") (pinfunction "7_7") (pintype "passive"))
      (node (ref "LPC1") (pin "23") (pinfunction "23_23") (pintype "passive"))
    )
    (net (code "252") (name "unconnected-(IC1-XERR-Pad23)") (class "Default")
      (node (ref "IC1") (pin "23") (pinfunction "XERR_23") (pintype "open_collector"))
    )
    (net (code "253") (name "unconnected-(IC2-XERR-Pad23)") (class "Default")
      (node (ref "IC2") (pin "23") (pinfunction "XERR_23") (pintype "open_collector"))
    )
    (net (code "254") (name "unconnected-(IC3-XERR-Pad23)") (class "Default")
      (node (ref "IC3") (pin "23") (pinfunction "XERR_23") (pintype "open_collector"))
    )
    (net (code "255") (name "unconnected-(IC4-XERR-Pad23)") (class "Default")
      (node (ref "IC4") (pin "23") (pinfunction "XERR_23") (pintype "open_collector"))
    )
    (net (code "256") (name "unconnected-(IC5-XERR-Pad23)") (class "Default")
      (node (ref "IC5") (pin "23") (pinfunction "XERR_23") (pintype "open_collector"))
    )
    (net (code "257") (name "unconnected-(IC6-XERR-Pad23)") (class "Default")
      (node (ref "IC6") (pin "23") (pinfunction "XERR_23") (pintype "open_collector"))
    )
    (net (code "258") (name "unconnected-(IC7-XERR-Pad23)") (class "Default")
      (node (ref "IC7") (pin "23") (pinfunction "XERR_23") (pintype "open_collector"))
    )
    (net (code "259") (name "unconnected-(IC8-XERR-Pad23)") (class "Default")
      (node (ref "IC8") (pin "23") (pinfunction "XERR_23") (pintype "open_collector"))
    )
    (net (code "260") (name "unconnected-(IC9-XERR-Pad23)") (class "Default")
      (node (ref "IC9") (pin "23") (pinfunction "XERR_23") (pintype "open_collector"))
    )
    (net (code "261") (name "unconnected-(IC10-XERR-Pad23)") (class "Default")
      (node (ref "IC10") (pin "23") (pinfunction "XERR_23") (pintype "open_collector"))
    )
    (net (code "262") (name "unconnected-(IC11-XERR-Pad23)") (class "Default")
      (node (ref "IC11") (pin "23") (pinfunction "XERR_23") (pintype "open_collector"))
    )
    (net (code "263") (name "unconnected-(IC12-XERR-Pad23)") (class "Default")
      (node (ref "IC12") (pin "23") (pinfunction "XERR_23") (pintype "open_collector"))
    )
    (net (code "264") (name "unconnected-(JP1-Pad11)") (class "Default")
      (node (ref "JP1") (pin "11") (pinfunction "11_11") (pintype "passive"))
    )
    (net (code "265") (name "unconnected-(JP1-Pad12)") (class "Default")
      (node (ref "JP1") (pin "12") (pinfunction "12_12") (pintype "passive"))
    )
    (net (code "266") (name "unconnected-(LPC1-Pad3)") (class "Default")
      (node (ref "LPC1") (pin "3") (pinfunction "3_3") (pintype "passive"))
    )
    (net (code "267") (name "unconnected-(LPC1-Pad5)") (class "Default")
      (node (ref "LPC1") (pin "5") (pinfunction "5_5") (pintype "passive"))
    )
    (net (code "268") (name "unconnected-(LPC1-Pad6)") (class "Default")
      (node (ref "LPC1") (pin "6") (pinfunction "6_6") (pintype "passive"))
    )
    (net (code "269") (name "unconnected-(LPC1-Pad7)") (class "Default")
      (node (ref "LPC1") (pin "7") (pinfunction "7_7") (pintype "passive"))
    )
    (net (code "270") (name "unconnected-(LPC1-Pad8)") (class "Default")
      (node (ref "LPC1") (pin "8") (pinfunction "8_8") (pintype "passive"))
    )
    (net (code "271") (name "unconnected-(LPC1-Pad12)") (class "Default")
      (node (ref "LPC1") (pin "12") (pinfunction "12_12") (pintype "passive"))
    )
    (net (code "272") (name "unconnected-(LPC1-Pad14)") (class "Default")
      (node (ref "LPC1") (pin "14") (pinfunction "14_14") (pintype "passive"))
    )
    (net (code "273") (name "unconnected-(LPC1-Pad15)") (class "Default")
      (node (ref "LPC1") (pin "15") (pinfunction "15_15") (pintype "passive"))
    )
    (net (code "274") (name "unconnected-(LPC1-Pad16)") (class "Default")
      (node (ref "LPC1") (pin "16") (pinfunction "16_16") (pintype "passive"))
    )
    (net (code "275") (name "unconnected-(LPC1-Pad17)") (class "Default")
      (node (ref "LPC1") (pin "17") (pinfunction "17_17") (pintype "passive"))
    )
    (net (code "276") (name "unconnected-(LPC1-Pad18)") (class "Default")
      (node (ref "LPC1") (pin "18") (pinfunction "18_18") (pintype "passive"))
    )
    (net (code "277") (name "unconnected-(LPC1-Pad19)") (class "Default")
      (node (ref "LPC1") (pin "19") (pinfunction "19_19") (pintype "passive"))
    )
    (net (code "278") (name "unconnected-(LPC1-Pad20)") (class "Default")
      (node (ref "LPC1") (pin "20") (pinfunction "20_20") (pintype "passive"))
    )
    (net (code "279") (name "unconnected-(LPC1-Pad21)") (class "Default")
      (node (ref "LPC1") (pin "21") (pinfunction "21_21") (pintype "passive"))
    )
    (net (code "280") (name "unconnected-(LPC1-Pad22)") (class "Default")
      (node (ref "LPC1") (pin "22") (pinfunction "22_22") (pintype "passive"))
    )
    (net (code "281") (name "unconnected-(LPC1-Pad27)") (class "Default")
      (node (ref "LPC1") (pin "27") (pinfunction "27_27") (pintype "passive"))
    )
    (net (code "282") (name "unconnected-(LPC1-Pad29)") (class "Default")
      (node (ref "LPC1") (pin "29") (pinfunction "29_29") (pintype "passive"))
    )
    (net (code "283") (name "unconnected-(LPC1-Pad30)") (class "Default")
      (node (ref "LPC1") (pin "30") (pinfunction "30_30") (pintype "passive"))
    )
    (net (code "284") (name "unconnected-(LPC1-Pad31)") (class "Default")
      (node (ref "LPC1") (pin "31") (pinfunction "31_31") (pintype "passive"))
    )
    (net (code "285") (name "unconnected-(LPC1-Pad32)") (class "Default")
      (node (ref "LPC1") (pin "32") (pinfunction "32_32") (pintype "passive"))
    )
    (net (code "286") (name "unconnected-(LPC1-Pad33)") (class "Default")
      (node (ref "LPC1") (pin "33") (pinfunction "33_33") (pintype "passive"))
    )
    (net (code "287") (name "unconnected-(LPC1-Pad34)") (class "Default")
      (node (ref "LPC1") (pin "34") (pinfunction "34_34") (pintype "passive"))
    )
    (net (code "288") (name "unconnected-(LPC1-Pad35)") (class "Default")
      (node (ref "LPC1") (pin "35") (pinfunction "35_35") (pintype "passive"))
    )
    (net (code "289") (name "unconnected-(LPC1-Pad36)") (class "Default")
      (node (ref "LPC1") (pin "36") (pinfunction "36_36") (pintype "passive"))
    )
    (net (code "290") (name "unconnected-(LPC1-Pad37)") (class "Default")
      (node (ref "LPC1") (pin "37") (pinfunction "37_37") (pintype "passive"))
    )
    (net (code "291") (name "unconnected-(LPC1-Pad38)") (class "Default")
      (node (ref "LPC1") (pin "38") (pinfunction "38_38") (pintype "passive"))
    )
    (net (code "292") (name "unconnected-(LPC1-Pad39)") (class "Default")
      (node (ref "LPC1") (pin "39") (pinfunction "39_39") (pintype "passive"))
    )
    (net (code "293") (name "unconnected-(LPC1-Pad43)") (class "Default")
      (node (ref "LPC1") (pin "43") (pinfunction "43_43") (pintype "passive"))
    )
    (net (code "294") (name "unconnected-(LPC1-Pad44)") (class "Default")
      (node (ref "LPC1") (pin "44") (pinfunction "44_44") (pintype "passive"))
    )
    (net (code "295") (name "unconnected-(LPC1-Pad45)") (class "Default")
      (node (ref "LPC1") (pin "45") (pinfunction "45_45") (pintype "passive"))
    )
    (net (code "296") (name "unconnected-(LPC1-Pad46)") (class "Default")
      (node (ref "LPC1") (pin "46") (pinfunction "46_46") (pintype "passive"))
    )
    (net (code "297") (name "unconnected-(LPC1-Pad47)") (class "Default")
      (node (ref "LPC1") (pin "47") (pinfunction "47_47") (pintype "passive"))
    )
    (net (code "298") (name "unconnected-(LPC1-Pad48)") (class "Default")
      (node (ref "LPC1") (pin "48") (pinfunction "48_48") (pintype "passive"))
    )
    (net (code "299") (name "unconnected-(LPC1-Pad49)") (class "Default")
      (node (ref "LPC1") (pin "49") (pinfunction "49_49") (pintype "passive"))
    )
    (net (code "300") (name "unconnected-(LPC1-Pad50)") (class "Default")
      (node (ref "LPC1") (pin "50") (pinfunction "50_50") (pintype "passive"))
    )
    (net (code "301") (name "unconnected-(LPC1-Pad51)") (class "Default")
      (node (ref "LPC1") (pin "51") (pinfunction "51_51") (pintype "passive"))
    )
    (net (code "302") (name "unconnected-(LPC1-Pad52)") (class "Default")
      (node (ref "LPC1") (pin "52") (pinfunction "52_52") (pintype "passive"))
    )
    (net (code "303") (name "unconnected-(LPC1-Pad53)") (class "Default")
      (node (ref "LPC1") (pin "53") (pinfunction "53_53") (pintype "passive"))
    )
    (net (code "304") (name "unconnected-(LPC1-Pad54)") (class "Default")
      (node (ref "LPC1") (pin "54") (pinfunction "54_54") (pintype "passive"))
    )
    (net (code "305") (name "unconnected-(LPC1-Pad55)") (class "Default")
      (node (ref "LPC1") (pin "55") (pinfunction "55_55") (pintype "passive"))
    )
    (net (code "306") (name "unconnected-(LPC1-Pad56)") (class "Default")
      (node (ref "LPC1") (pin "56") (pinfunction "56_56") (pintype "passive"))
    )
    (net (code "307") (name "unconnected-(LPC1-Pad57)") (class "Default")
      (node (ref "LPC1") (pin "57") (pinfunction "57_57") (pintype "passive"))
    )
    (net (code "308") (name "unconnected-(LPC1-Pad58)") (class "Default")
      (node (ref "LPC1") (pin "58") (pinfunction "58_58") (pintype "passive"))
    )
    (net (code "309") (name "unconnected-(LPC1-Pad59)") (class "Default")
      (node (ref "LPC1") (pin "59") (pinfunction "59_59") (pintype "passive"))
    )
    (net (code "310") (name "unconnected-(LPC1-Pad60)") (class "Default")
      (node (ref "LPC1") (pin "60") (pinfunction "60_60") (pintype "passive"))
    )
    (net (code "311") (name "unconnected-(LPC1-Pad61)") (class "Default")
      (node (ref "LPC1") (pin "61") (pinfunction "61_61") (pintype "passive"))
    )
    (net (code "312") (name "unconnected-(LPC1-Pad62)") (class "Default")
      (node (ref "LPC1") (pin "62") (pinfunction "62_62") (pintype "passive"))
    )
    (net (code "313") (name "unconnected-(LPC1-Pad63)") (class "Default")
      (node (ref "LPC1") (pin "63") (pinfunction "63_63") (pintype "passive"))
    )
    (net (code "314") (name "unconnected-(LPC1-Pad64)") (class "Default")
      (node (ref "LPC1") (pin "64") (pinfunction "64_64") (pintype "passive"))
    )
    (net (code "315") (name "unconnected-(LPC1-Pad65)") (class "Default")
      (node (ref "LPC1") (pin "65") (pinfunction "65_65") (pintype "passive"))
    )
    (net (code "316") (name "unconnected-(S1-P-Pad3)") (class "Default")
      (node (ref "S1") (pin "3") (pinfunction "P_3") (pintype "passive"))
    )
    (net (code "317") (name "unconnected-(S1-S1-Pad2)") (class "Default")
      (node (ref "S1") (pin "2") (pinfunction "S1_2") (pintype "passive"))
    )
  )
)
